# PCB.net
KiCad netlist of a schematic drawn in EAGLE
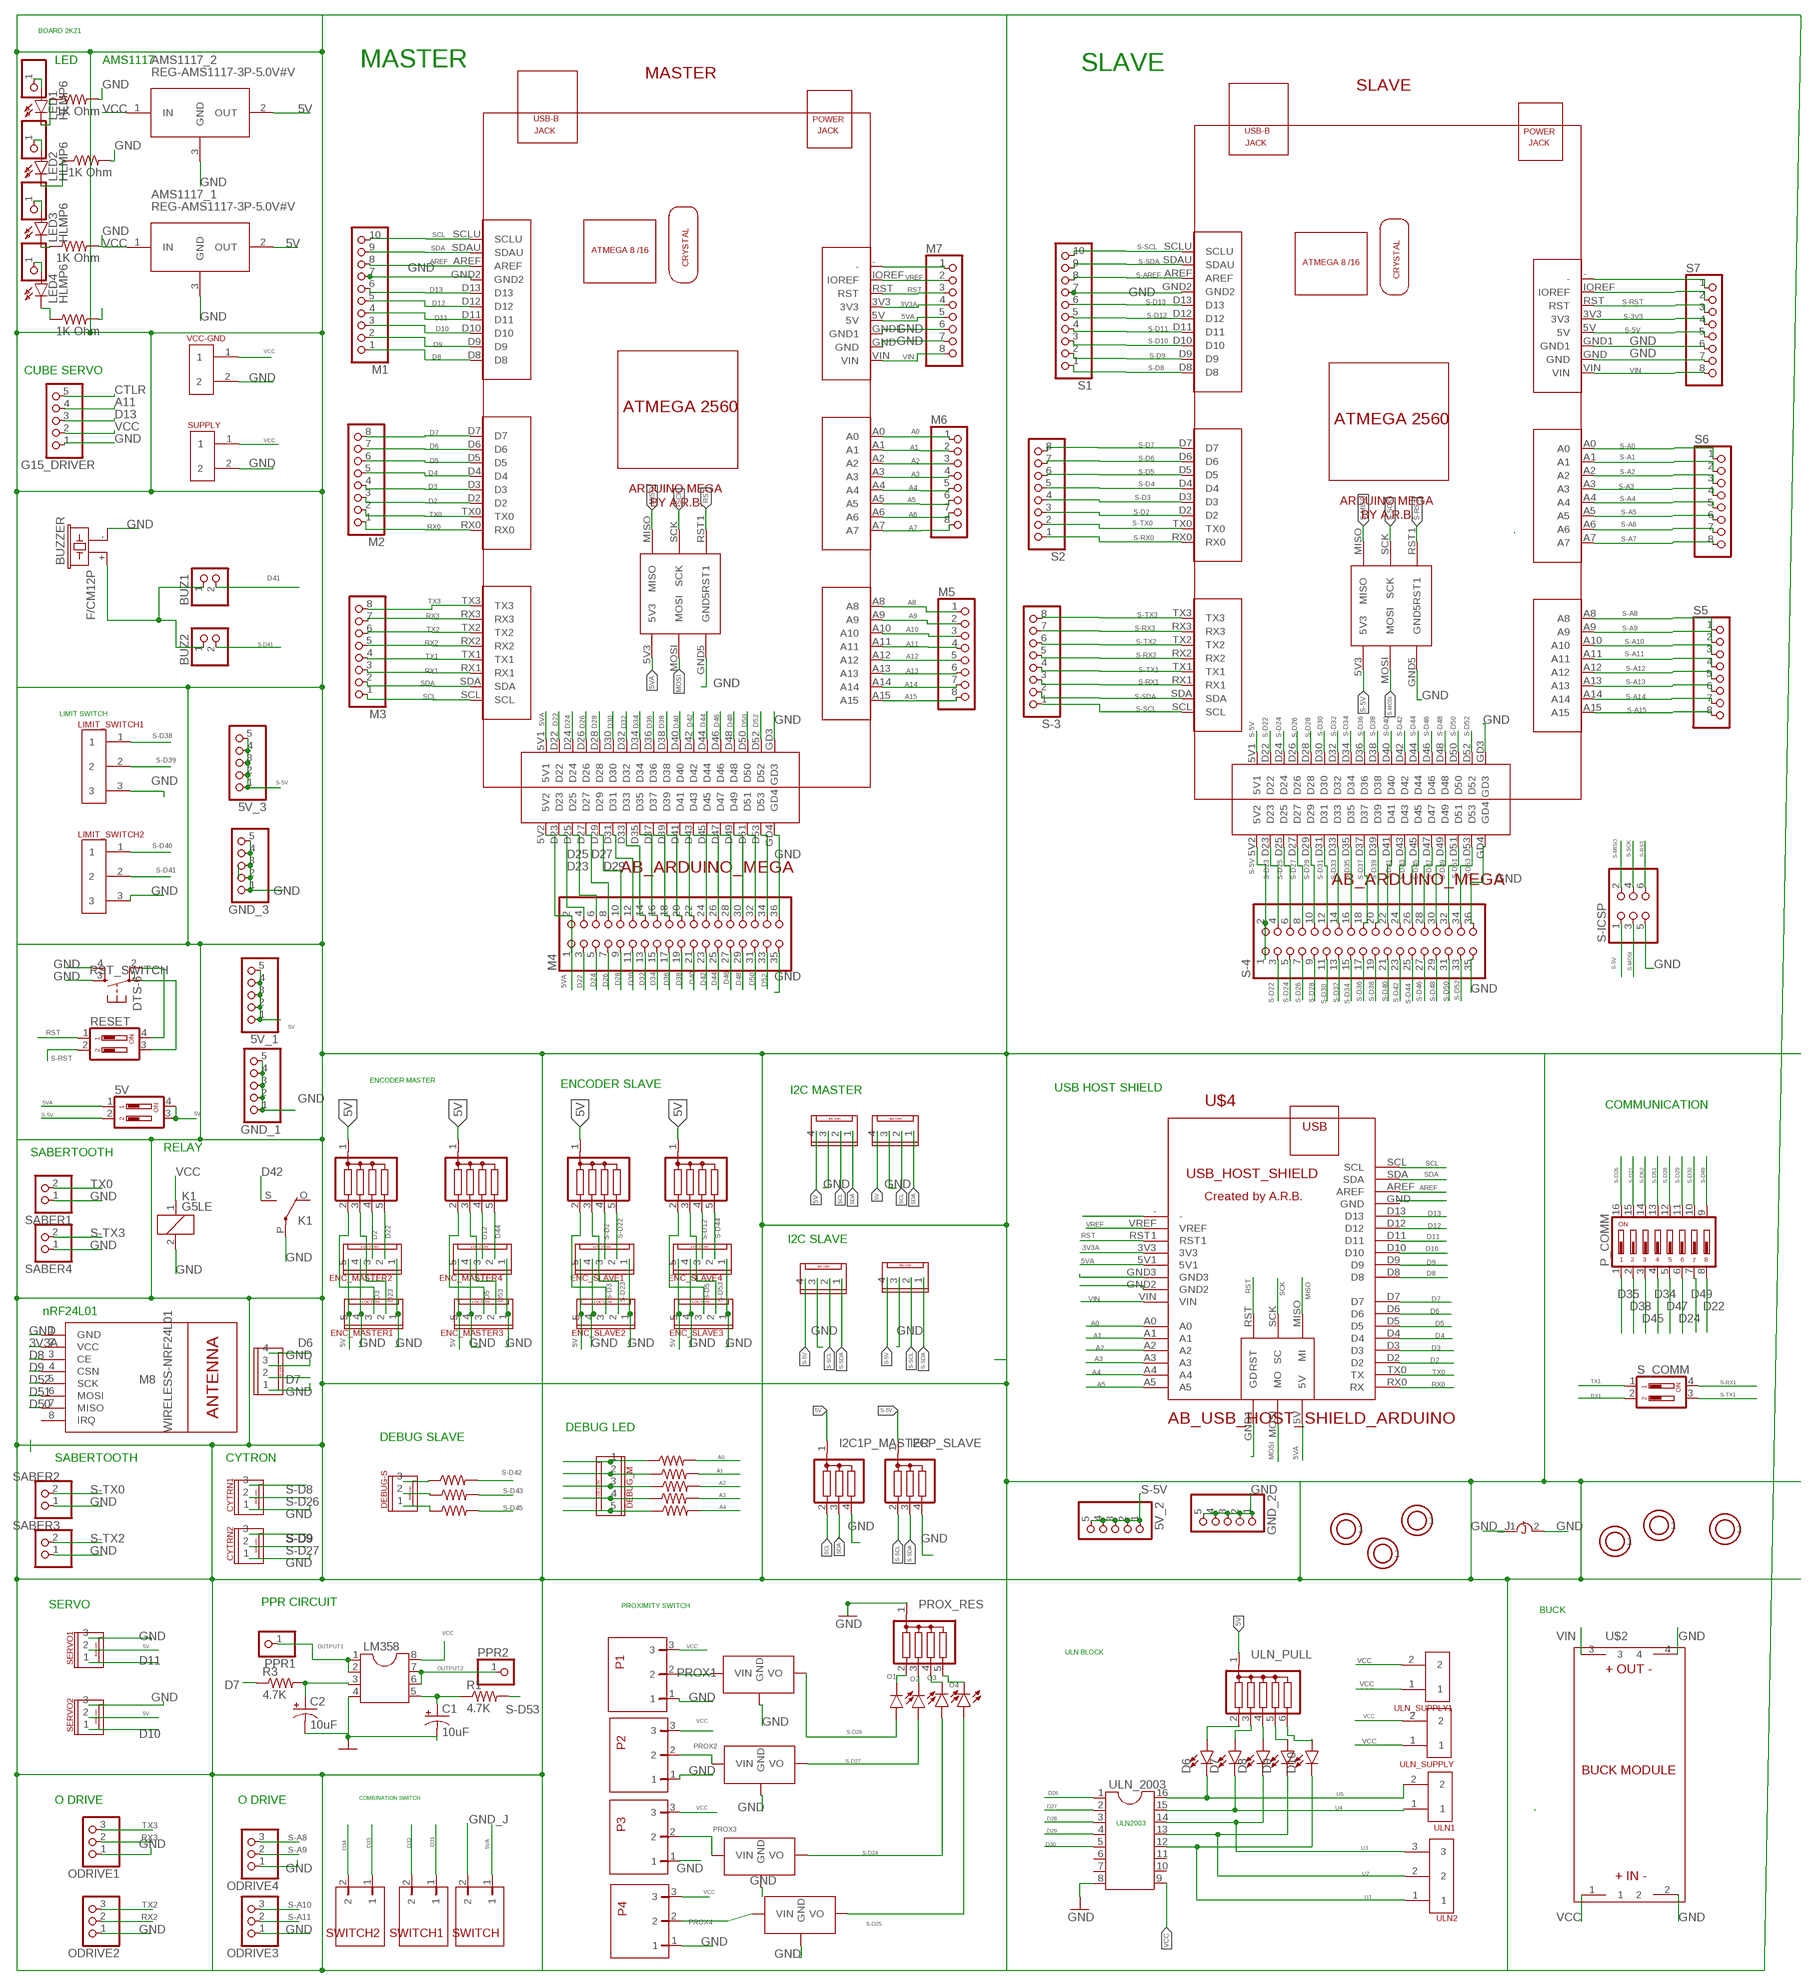
[diagram p0: schematic, sheet 1]

(export (version "E")
  (design (tool "Eeschema 10.0.6"))
  (components
    (comp (ref "5V")
      (value "DIP02YL")
      (footprint "eagle-import:DIP02YL")
      (libsource (lib "eagle-import") (part "DIP02YL"))
    )
    (comp (ref "5V_1")
      (value "PINHD-1X5")
      (footprint "eagle-import:1X05")
      (libsource (lib "eagle-import") (part "PINHD-1X5"))
    )
    (comp (ref "5V_2")
      (value "PINHD-1X5")
      (footprint "eagle-import:1X05")
      (libsource (lib "eagle-import") (part "PINHD-1X5"))
    )
    (comp (ref "5V_3")
      (value "PINHD-1X5")
      (footprint "eagle-import:1X05")
      (libsource (lib "eagle-import") (part "PINHD-1X5"))
    )
    (comp (ref "AMS1117_1")
      (value "REG-AMS1117-3P-5.0V#V")
      (footprint "eagle-import:REG-AMS1117-3P#V")
      (libsource (lib "eagle-import") (part "REG-AMS1117-3P-#V5.0V"))
    )
    (comp (ref "AMS1117_2")
      (value "REG-AMS1117-3P-5.0V#V")
      (footprint "eagle-import:REG-AMS1117-3P#V")
      (libsource (lib "eagle-import") (part "REG-AMS1117-3P-#V5.0V"))
    )
    (comp (ref "BUZ1")
      (value "PINHD-1X2")
      (footprint "eagle-import:1X02")
      (libsource (lib "eagle-import") (part "PINHD-1X2"))
    )
    (comp (ref "BUZ2")
      (value "PINHD-1X2")
      (footprint "eagle-import:1X02")
      (libsource (lib "eagle-import") (part "PINHD-1X2"))
    )
    (comp (ref "BUZZER")
      (value "F/CM12P")
      (footprint "eagle-import:F_CM12P")
      (libsource (lib "eagle-import") (part "F/CM12P"))
    )
    (comp (ref "C1")
      (value "10uF")
      (footprint "eagle-import:CPOL-RADIAL-2.5MM-5MM")
      (libsource (lib "eagle-import") (part "10UF-POLAR-RADIAL-2.5MM-25V-20%"))
    )
    (comp (ref "C2")
      (value "10uF")
      (footprint "eagle-import:CPOL-RADIAL-2.5MM-5MM")
      (libsource (lib "eagle-import") (part "10UF-POLAR-RADIAL-2.5MM-25V-20%"))
    )
    (comp (ref "CYTRN1")
      (value "AB_3PIN_LOC_CONNECTOR")
      (footprint "eagle-import:AB_3PIN_LOC_CONNECTOR")
      (libsource (lib "eagle-import") (part "AB_3PIN_LOC_CONNECTOR"))
    )
    (comp (ref "CYTRN2")
      (value "AB_3PIN_LOC_CONNECTOR")
      (footprint "eagle-import:AB_3PIN_LOC_CONNECTOR")
      (libsource (lib "eagle-import") (part "AB_3PIN_LOC_CONNECTOR"))
    )
    (comp (ref "D1")
      (value "LED-3MM-NO_SILK")
      (footprint "eagle-import:LED_3MM-NS")
      (libsource (lib "eagle-import") (part "LED-3MM-NO_SILK"))
    )
    (comp (ref "D2")
      (value "LED-3MM-NO_SILK")
      (footprint "eagle-import:LED_3MM-NS")
      (libsource (lib "eagle-import") (part "LED-3MM-NO_SILK"))
    )
    (comp (ref "D3")
      (value "LED-3MM-NO_SILK")
      (footprint "eagle-import:LED_3MM-NS")
      (libsource (lib "eagle-import") (part "LED-3MM-NO_SILK"))
    )
    (comp (ref "D6")
      (value "LED-3MM-NO_SILK")
      (footprint "eagle-import:LED_3MM-NS")
      (libsource (lib "eagle-import") (part "LED-3MM-NO_SILK"))
    )
    (comp (ref "D7")
      (value "LED-3MM-NO_SILK")
      (footprint "eagle-import:LED_3MM-NS")
      (libsource (lib "eagle-import") (part "LED-3MM-NO_SILK"))
    )
    (comp (ref "D8")
      (value "LED-3MM-NO_SILK")
      (footprint "eagle-import:LED_3MM-NS")
      (libsource (lib "eagle-import") (part "LED-3MM-NO_SILK"))
    )
    (comp (ref "D9")
      (value "LED-3MM-NO_SILK")
      (footprint "eagle-import:LED_3MM-NS")
      (libsource (lib "eagle-import") (part "LED-3MM-NO_SILK"))
    )
    (comp (ref "D10")
      (value "LED-3MM-NO_SILK")
      (footprint "eagle-import:LED_3MM-NS")
      (libsource (lib "eagle-import") (part "LED-3MM-NO_SILK"))
    )
    (comp (ref "D14")
      (value "LED-3MM-NO_SILK")
      (footprint "eagle-import:LED_3MM-NS")
      (libsource (lib "eagle-import") (part "LED-3MM-NO_SILK"))
    )
    (comp (ref "DEBUG-S")
      (value "AB_3PIN_LOC_CONNECTOR")
      (footprint "eagle-import:AB_3PIN_LOC_CONNECTOR")
      (libsource (lib "eagle-import") (part "AB_3PIN_LOC_CONNECTOR"))
    )
    (comp (ref "DEBUG_M")
      (value "AB_5PIN_LOC_CONNECTOR")
      (footprint "eagle-import:AB_5PIN_LOC_CONNECTOR")
      (libsource (lib "eagle-import") (part "AB_5PIN_LOC_CONNECTOR"))
    )
    (comp (ref "ENC_MASTER1")
      (value "AB_5PIN_LOC_CONNECTOR")
      (footprint "eagle-import:AB_5PIN_LOC_CONNECTOR")
      (libsource (lib "eagle-import") (part "AB_5PIN_LOC_CONNECTOR"))
    )
    (comp (ref "ENC_MASTER2")
      (value "AB_5PIN_LOC_CONNECTOR")
      (footprint "eagle-import:AB_5PIN_LOC_CONNECTOR")
      (libsource (lib "eagle-import") (part "AB_5PIN_LOC_CONNECTOR"))
    )
    (comp (ref "ENC_MASTER3")
      (value "AB_5PIN_LOC_CONNECTOR")
      (footprint "eagle-import:AB_5PIN_LOC_CONNECTOR")
      (libsource (lib "eagle-import") (part "AB_5PIN_LOC_CONNECTOR"))
    )
    (comp (ref "ENC_MASTER4")
      (value "AB_5PIN_LOC_CONNECTOR")
      (footprint "eagle-import:AB_5PIN_LOC_CONNECTOR")
      (libsource (lib "eagle-import") (part "AB_5PIN_LOC_CONNECTOR"))
    )
    (comp (ref "ENC_SLAVE1")
      (value "AB_5PIN_LOC_CONNECTOR")
      (footprint "eagle-import:AB_5PIN_LOC_CONNECTOR")
      (libsource (lib "eagle-import") (part "AB_5PIN_LOC_CONNECTOR"))
    )
    (comp (ref "ENC_SLAVE2")
      (value "AB_5PIN_LOC_CONNECTOR")
      (footprint "eagle-import:AB_5PIN_LOC_CONNECTOR")
      (libsource (lib "eagle-import") (part "AB_5PIN_LOC_CONNECTOR"))
    )
    (comp (ref "ENC_SLAVE3")
      (value "AB_5PIN_LOC_CONNECTOR")
      (footprint "eagle-import:AB_5PIN_LOC_CONNECTOR")
      (libsource (lib "eagle-import") (part "AB_5PIN_LOC_CONNECTOR"))
    )
    (comp (ref "ENC_SLAVE4")
      (value "AB_5PIN_LOC_CONNECTOR")
      (footprint "eagle-import:AB_5PIN_LOC_CONNECTOR")
      (libsource (lib "eagle-import") (part "AB_5PIN_LOC_CONNECTOR"))
    )
    (comp (ref "G15_DRIVER")
      (value "PINHD-1X5")
      (footprint "eagle-import:1X05")
      (libsource (lib "eagle-import") (part "PINHD-1X5"))
    )
    (comp (ref "GND_1")
      (value "PINHD-1X5")
      (footprint "eagle-import:1X05")
      (libsource (lib "eagle-import") (part "PINHD-1X5"))
    )
    (comp (ref "GND_2")
      (value "PINHD-1X5")
      (footprint "eagle-import:1X05")
      (libsource (lib "eagle-import") (part "PINHD-1X5"))
    )
    (comp (ref "GND_3")
      (value "PINHD-1X5")
      (footprint "eagle-import:1X05")
      (libsource (lib "eagle-import") (part "PINHD-1X5"))
    )
    (comp (ref "I2C1P_MASTER")
      (value "G03R")
      (footprint "eagle-import:SIL4")
      (libsource (lib "eagle-import") (part "G03R"))
    )
    (comp (ref "I2CP_SLAVE")
      (value "G03R")
      (footprint "eagle-import:SIL4")
      (libsource (lib "eagle-import") (part "G03R"))
    )
    (comp (ref "IMU_BLOCK2")
      (value "AB_4PIN_LOC_CONNECTOR")
      (footprint "eagle-import:AB_4PIN_LOC_CONNECTOR")
      (libsource (lib "eagle-import") (part "AB_4PIN_LOC_CONNECTOR"))
    )
    (comp (ref "IMU_BLOCK3")
      (value "AB_4PIN_LOC_CONNECTOR")
      (footprint "eagle-import:AB_4PIN_LOC_CONNECTOR")
      (libsource (lib "eagle-import") (part "AB_4PIN_LOC_CONNECTOR"))
    )
    (comp (ref "IMU_BLOCK4")
      (value "AB_4PIN_LOC_CONNECTOR")
      (footprint "eagle-import:AB_4PIN_LOC_CONNECTOR")
      (libsource (lib "eagle-import") (part "AB_4PIN_LOC_CONNECTOR"))
    )
    (comp (ref "IMU_MASTER")
      (value "AB_4PIN_LOC_CONNECTOR")
      (footprint "eagle-import:AB_4PIN_LOC_CONNECTOR")
      (libsource (lib "eagle-import") (part "AB_4PIN_LOC_CONNECTOR"))
    )
    (comp (ref "K1")
      (value "G5LE")
      (footprint "eagle-import:G5LE")
      (libsource (lib "eagle-import") (part "G5LE"))
    )
    (comp (ref "LED1")
      (value "HLMP6")
      (footprint "eagle-import:HLMP6")
      (fields (field (name "MF") "AGILENT TECHNOLOGIES") (field (name "MPN") "HLMP-6500"))
      (libsource (lib "eagle-import") (part "HLMP6"))
    )
    (comp (ref "LED2")
      (value "HLMP6")
      (footprint "eagle-import:HLMP6")
      (fields (field (name "MF") "AGILENT TECHNOLOGIES") (field (name "MPN") "HLMP-6500"))
      (libsource (lib "eagle-import") (part "HLMP6"))
    )
    (comp (ref "LED3")
      (value "HLMP6")
      (footprint "eagle-import:HLMP6")
      (fields (field (name "MF") "AGILENT TECHNOLOGIES") (field (name "MPN") "HLMP-6500"))
      (libsource (lib "eagle-import") (part "HLMP6"))
    )
    (comp (ref "LED4")
      (value "HLMP6")
      (footprint "eagle-import:HLMP6")
      (fields (field (name "MF") "AGILENT TECHNOLOGIES") (field (name "MPN") "HLMP-6500"))
      (libsource (lib "eagle-import") (part "HLMP6"))
    )
    (comp (ref "LIMIT_SWITCH1")
      (value "AB_SCREW_TER_5MM_3PIN")
      (footprint "eagle-import:AB_SCREW_TER_5MM_3PIN")
      (libsource (lib "eagle-import") (part "AB_SCREW_TER_5MM_3PIN"))
    )
    (comp (ref "LIMIT_SWITCH2")
      (value "AB_SCREW_TER_5MM_3PIN")
      (footprint "eagle-import:AB_SCREW_TER_5MM_3PIN")
      (libsource (lib "eagle-import") (part "AB_SCREW_TER_5MM_3PIN"))
    )
    (comp (ref "LM358")
      (value "DIL8")
      (footprint "eagle-import:DIL08")
      (libsource (lib "eagle-import") (part "DIL8"))
    )
    (comp (ref "M1")
      (value "PINHD-1X10")
      (footprint "eagle-import:1X10")
      (libsource (lib "eagle-import") (part "PINHD-1X10"))
    )
    (comp (ref "M2")
      (value "PINHD-1X8")
      (footprint "eagle-import:1X08")
      (libsource (lib "eagle-import") (part "PINHD-1X8"))
    )
    (comp (ref "M3")
      (value "PINHD-1X8")
      (footprint "eagle-import:1X08")
      (libsource (lib "eagle-import") (part "PINHD-1X8"))
    )
    (comp (ref "M4")
      (value "PINHD-2X18")
      (footprint "eagle-import:2X18")
      (libsource (lib "eagle-import") (part "PINHD-2X18"))
    )
    (comp (ref "M5")
      (value "PINHD-1X8")
      (footprint "eagle-import:1X08")
      (libsource (lib "eagle-import") (part "PINHD-1X8"))
    )
    (comp (ref "M6")
      (value "PINHD-1X8")
      (footprint "eagle-import:1X08")
      (libsource (lib "eagle-import") (part "PINHD-1X8"))
    )
    (comp (ref "M7")
      (value "PINHD-1X8")
      (footprint "eagle-import:1X08")
      (libsource (lib "eagle-import") (part "PINHD-1X8"))
    )
    (comp (ref "M8")
      (value "WIRELESS-NRF24L01")
      (footprint "eagle-import:WIRELESS-NRF24L01")
      (libsource (lib "eagle-import") (part "WIRELESS-NRF24L01"))
    )
    (comp (ref "MASTER")
      (value "AB_ARDUINO_MEGA")
      (footprint "eagle-import:AB_ARDUINO_MEGA")
      (libsource (lib "eagle-import") (part "AB_ARDUINO_MEGA"))
    )
    (comp (ref "ODRIVE1")
      (value "PINHD-1X3")
      (footprint "eagle-import:1X03")
      (libsource (lib "eagle-import") (part "PINHD-1X3"))
    )
    (comp (ref "ODRIVE2")
      (value "PINHD-1X3")
      (footprint "eagle-import:1X03")
      (libsource (lib "eagle-import") (part "PINHD-1X3"))
    )
    (comp (ref "ODRIVE3")
      (value "PINHD-1X3")
      (footprint "eagle-import:1X03")
      (libsource (lib "eagle-import") (part "PINHD-1X3"))
    )
    (comp (ref "ODRIVE4")
      (value "PINHD-1X3")
      (footprint "eagle-import:1X03")
      (libsource (lib "eagle-import") (part "PINHD-1X3"))
    )
    (comp (ref "P1")
      (value "P1")
      (footprint "eagle-import:AB_RIGHT_TER_BLK_3PIN")
      (libsource (lib "eagle-import") (part "AB_RIGHT_TER_BLK_3PIN"))
    )
    (comp (ref "P2")
      (value "P2")
      (footprint "eagle-import:AB_RIGHT_TER_BLK_3PIN")
      (libsource (lib "eagle-import") (part "AB_RIGHT_TER_BLK_3PIN"))
    )
    (comp (ref "P3")
      (value "P3")
      (footprint "eagle-import:AB_RIGHT_TER_BLK_3PIN")
      (libsource (lib "eagle-import") (part "AB_RIGHT_TER_BLK_3PIN"))
    )
    (comp (ref "P4")
      (value "P4")
      (footprint "eagle-import:AB_RIGHT_TER_BLK_3PIN")
      (libsource (lib "eagle-import") (part "AB_RIGHT_TER_BLK_3PIN"))
    )
    (comp (ref "PPR1")
      (value "PINHD-1X1")
      (footprint "eagle-import:1X01")
      (libsource (lib "eagle-import") (part "PINHD-1X1"))
    )
    (comp (ref "PPR2")
      (value "PINHD-1X1")
      (footprint "eagle-import:1X01")
      (libsource (lib "eagle-import") (part "PINHD-1X1"))
    )
    (comp (ref "PPR5")
      (value "PINHD-1X1")
      (footprint "eagle-import:1X01")
      (libsource (lib "eagle-import") (part "PINHD-1X1"))
    )
    (comp (ref "PPR6")
      (value "PINHD-1X1")
      (footprint "eagle-import:1X01")
      (libsource (lib "eagle-import") (part "PINHD-1X1"))
    )
    (comp (ref "PPR7")
      (value "PINHD-1X1")
      (footprint "eagle-import:1X01")
      (libsource (lib "eagle-import") (part "PINHD-1X1"))
    )
    (comp (ref "PPR8")
      (value "PINHD-1X1")
      (footprint "eagle-import:1X01")
      (libsource (lib "eagle-import") (part "PINHD-1X1"))
    )
    (comp (ref "PROX_RES")
      (value "G04R")
      (footprint "eagle-import:SIL5")
      (libsource (lib "eagle-import") (part "G04R"))
    )
    (comp (ref "PULL_MASTER1")
      (value "G04R")
      (footprint "eagle-import:SIL5")
      (libsource (lib "eagle-import") (part "G04R"))
    )
    (comp (ref "PULL_MASTER2")
      (value "G04R")
      (footprint "eagle-import:SIL5")
      (libsource (lib "eagle-import") (part "G04R"))
    )
    (comp (ref "PULL_SLAVE3")
      (value "G04R")
      (footprint "eagle-import:SIL5")
      (libsource (lib "eagle-import") (part "G04R"))
    )
    (comp (ref "P_COMM")
      (value "DIP08YL")
      (footprint "eagle-import:DIP08YL")
      (libsource (lib "eagle-import") (part "DIP08YL"))
    )
    (comp (ref "R1")
      (value "4.7K")
      (footprint "eagle-import:0204_7")
      (libsource (lib "eagle-import") (part "R-US_0204/7"))
    )
    (comp (ref "R2")
      (value "R-US_0204/7")
      (footprint "eagle-import:0204_7")
      (libsource (lib "eagle-import") (part "R-US_0204/7"))
    )
    (comp (ref "R3")
      (value "4.7K")
      (footprint "eagle-import:0204_7")
      (libsource (lib "eagle-import") (part "R-US_0204/7"))
    )
    (comp (ref "R4")
      (value "R-US_0204/7")
      (footprint "eagle-import:0204_7")
      (libsource (lib "eagle-import") (part "R-US_0204/7"))
    )
    (comp (ref "R5")
      (value "R-US_0204/7")
      (footprint "eagle-import:0204_7")
      (libsource (lib "eagle-import") (part "R-US_0204/7"))
    )
    (comp (ref "R6")
      (value "R-US_0204/7")
      (footprint "eagle-import:0204_7")
      (libsource (lib "eagle-import") (part "R-US_0204/7"))
    )
    (comp (ref "R7")
      (value "R-US_0204/7")
      (footprint "eagle-import:0204_7")
      (libsource (lib "eagle-import") (part "R-US_0204/7"))
    )
    (comp (ref "R8")
      (value "R-US_0204/7")
      (footprint "eagle-import:0204_7")
      (libsource (lib "eagle-import") (part "R-US_0204/7"))
    )
    (comp (ref "R9")
      (value "R-US_0204/7")
      (footprint "eagle-import:0204_7")
      (libsource (lib "eagle-import") (part "R-US_0204/7"))
    )
    (comp (ref "R10")
      (value "R-US_0204/7")
      (footprint "eagle-import:0204_7")
      (libsource (lib "eagle-import") (part "R-US_0204/7"))
    )
    (comp (ref "R13")
      (value "1K Ohm")
      (footprint "eagle-import:0204_7")
      (libsource (lib "eagle-import") (part "R-US_0204/7"))
    )
    (comp (ref "R14")
      (value "1K Ohm")
      (footprint "eagle-import:0204_7")
      (libsource (lib "eagle-import") (part "R-US_0204/7"))
    )
    (comp (ref "R15")
      (value "1K Ohm")
      (footprint "eagle-import:0204_7")
      (libsource (lib "eagle-import") (part "R-US_0204/7"))
    )
    (comp (ref "R16")
      (value "1K Ohm")
      (footprint "eagle-import:0204_7")
      (libsource (lib "eagle-import") (part "R-US_0204/7"))
    )
    (comp (ref "RESET")
      (value "DIP02YL")
      (footprint "eagle-import:DIP02YL")
      (libsource (lib "eagle-import") (part "DIP02YL"))
    )
    (comp (ref "RST_SWITCH")
      (value "DTS-6")
      (footprint "eagle-import:DTS-6")
      (libsource (lib "eagle-import") (part "DTS-6"))
    )
    (comp (ref "S-3")
      (value "PINHD-1X8")
      (footprint "eagle-import:1X08")
      (libsource (lib "eagle-import") (part "PINHD-1X8"))
    )
    (comp (ref "S-4")
      (value "PINHD-2X18")
      (footprint "eagle-import:2X18")
      (libsource (lib "eagle-import") (part "PINHD-2X18"))
    )
    (comp (ref "S-ICSP")
      (value "PINHD-2X3")
      (footprint "eagle-import:2X03")
      (libsource (lib "eagle-import") (part "PINHD-2X3"))
    )
    (comp (ref "S1")
      (value "PINHD-1X10")
      (footprint "eagle-import:1X10")
      (libsource (lib "eagle-import") (part "PINHD-1X10"))
    )
    (comp (ref "S2")
      (value "PINHD-1X8")
      (footprint "eagle-import:1X08")
      (libsource (lib "eagle-import") (part "PINHD-1X8"))
    )
    (comp (ref "S5")
      (value "PINHD-1X8")
      (footprint "eagle-import:1X08")
      (libsource (lib "eagle-import") (part "PINHD-1X8"))
    )
    (comp (ref "S6")
      (value "PINHD-1X8")
      (footprint "eagle-import:1X08")
      (libsource (lib "eagle-import") (part "PINHD-1X8"))
    )
    (comp (ref "S7")
      (value "PINHD-1X8")
      (footprint "eagle-import:1X08")
      (libsource (lib "eagle-import") (part "PINHD-1X8"))
    )
    (comp (ref "SABER1")
      (value "PINHD-1X2")
      (footprint "eagle-import:1X02")
      (libsource (lib "eagle-import") (part "PINHD-1X2"))
    )
    (comp (ref "SABER2")
      (value "PINHD-1X2")
      (footprint "eagle-import:1X02")
      (libsource (lib "eagle-import") (part "PINHD-1X2"))
    )
    (comp (ref "SABER3")
      (value "PINHD-1X2")
      (footprint "eagle-import:1X02")
      (libsource (lib "eagle-import") (part "PINHD-1X2"))
    )
    (comp (ref "SABER4")
      (value "PINHD-1X2")
      (footprint "eagle-import:1X02")
      (libsource (lib "eagle-import") (part "PINHD-1X2"))
    )
    (comp (ref "SERVO1")
      (value "AB_3PIN_LOC_CONNECTOR")
      (footprint "eagle-import:AB_3PIN_LOC_CONNECTOR")
      (libsource (lib "eagle-import") (part "AB_3PIN_LOC_CONNECTOR"))
    )
    (comp (ref "SERVO2")
      (value "AB_3PIN_LOC_CONNECTOR")
      (footprint "eagle-import:AB_3PIN_LOC_CONNECTOR")
      (libsource (lib "eagle-import") (part "AB_3PIN_LOC_CONNECTOR"))
    )
    (comp (ref "SLAVE")
      (value "AB_ARDUINO_MEGA")
      (footprint "eagle-import:AB_ARDUINO_MEGA")
      (libsource (lib "eagle-import") (part "AB_ARDUINO_MEGA"))
    )
    (comp (ref "STEPPER")
      (value "AB_4PIN_LOC_CONNECTOR")
      (footprint "eagle-import:AB_4PIN_LOC_CONNECTOR")
      (libsource (lib "eagle-import") (part "AB_4PIN_LOC_CONNECTOR"))
    )
    (comp (ref "SUPPLY")
      (value "AB_SCREW_TERMINAL_5MM_2PIN")
      (footprint "eagle-import:AB_SCREW_TERMINAL_5MM_2PIN")
      (libsource (lib "eagle-import") (part "AB_SCREW_TERMINAL_5MM_2PIN"))
    )
    (comp (ref "SWITCH")
      (value "AB_RIGHT_TER_BLK")
      (footprint "eagle-import:AB_RIGHT_TER_BLK")
      (libsource (lib "eagle-import") (part "AB_RIGHT_TER_BLK"))
    )
    (comp (ref "SWITCH1")
      (value "AB_RIGHT_TER_BLK")
      (footprint "eagle-import:AB_RIGHT_TER_BLK")
      (libsource (lib "eagle-import") (part "AB_RIGHT_TER_BLK"))
    )
    (comp (ref "SWITCH2")
      (value "AB_RIGHT_TER_BLK")
      (footprint "eagle-import:AB_RIGHT_TER_BLK")
      (libsource (lib "eagle-import") (part "AB_RIGHT_TER_BLK"))
    )
    (comp (ref "S_COMM")
      (value "DIP02YL")
      (footprint "eagle-import:DIP02YL")
      (libsource (lib "eagle-import") (part "DIP02YL"))
    )
    (comp (ref "S_ENC_PULL1")
      (value "G04R")
      (footprint "eagle-import:SIL5")
      (libsource (lib "eagle-import") (part "G04R"))
    )
    (comp (ref "U$2")
      (value "BUCK_MODULEWITH_SMDPADS&THROUGHHOLES")
      (footprint "eagle-import:BUCK_MODULE")
      (libsource (lib "eagle-import") (part "BUCK_MODULEWITH_SMDPADS&THROUGHHOLES"))
    )
    (comp (ref "U$3")
      (value "PLATED_DRILL_3.5MM")
      (footprint "eagle-import:PLATED_DRILL_3.5MM")
      (libsource (lib "eagle-import") (part "PLATED_DRILL_3.5MM"))
    )
    (comp (ref "U$4")
      (value "AB_USB_HOST_SHIELD_ARDUINO")
      (footprint "eagle-import:AB_USB_HOST_SHIELD_ARDUINO")
      (libsource (lib "eagle-import") (part "AB_USB_HOST_SHIELD_ARDUINO"))
    )
    (comp (ref "U$5")
      (value "PLATED_DRILL_3.5MM")
      (footprint "eagle-import:PLATED_DRILL_3.5MM")
      (libsource (lib "eagle-import") (part "PLATED_DRILL_3.5MM"))
    )
    (comp (ref "U$6")
      (value "PLATED_DRILL_3.5MM")
      (footprint "eagle-import:PLATED_DRILL_3.5MM")
      (libsource (lib "eagle-import") (part "PLATED_DRILL_3.5MM"))
    )
    (comp (ref "U$7")
      (value "PLATED_DRILL_3.5MM")
      (footprint "eagle-import:PLATED_DRILL_3.5MM")
      (libsource (lib "eagle-import") (part "PLATED_DRILL_3.5MM"))
    )
    (comp (ref "U$8")
      (value "PLATED_DRILL_3.5MM")
      (footprint "eagle-import:PLATED_DRILL_3.5MM")
      (libsource (lib "eagle-import") (part "PLATED_DRILL_3.5MM"))
    )
    (comp (ref "U$9")
      (value "PLATED_DRILL_3.5MM")
      (footprint "eagle-import:PLATED_DRILL_3.5MM")
      (libsource (lib "eagle-import") (part "PLATED_DRILL_3.5MM"))
    )
    (comp (ref "U$23")
      (value "AB_7805_FLAT")
      (footprint "eagle-import:AB_7805_FLAT")
      (libsource (lib "eagle-import") (part "AB_7805_FLAT"))
    )
    (comp (ref "U$24")
      (value "AB_7805_FLAT")
      (footprint "eagle-import:AB_7805_FLAT")
      (libsource (lib "eagle-import") (part "AB_7805_FLAT"))
    )
    (comp (ref "U$25")
      (value "AB_7805_FLAT")
      (footprint "eagle-import:AB_7805_FLAT")
      (libsource (lib "eagle-import") (part "AB_7805_FLAT"))
    )
    (comp (ref "U$26")
      (value "AB_7805_FLAT")
      (footprint "eagle-import:AB_7805_FLAT")
      (libsource (lib "eagle-import") (part "AB_7805_FLAT"))
    )
    (comp (ref "U$35")
      (value "AB_JUMPER_ONE_WAY")
      (footprint "eagle-import:AB_JUMPER_ONE_WAY")
      (libsource (lib "eagle-import") (part "AB_JUMPER_ONE_WAY"))
    )
    (comp (ref "ULN1")
      (value "AB_SCREW_TERMINAL_5MM_2PIN")
      (footprint "eagle-import:AB_SCREW_TERMINAL_5MM_2PIN")
      (libsource (lib "eagle-import") (part "AB_SCREW_TERMINAL_5MM_2PIN"))
    )
    (comp (ref "ULN2")
      (value "AB_SCREW_TER_5MM_3PIN")
      (footprint "eagle-import:AB_SCREW_TER_5MM_3PIN")
      (libsource (lib "eagle-import") (part "AB_SCREW_TER_5MM_3PIN"))
    )
    (comp (ref "ULN_2003")
      (value "DIL16")
      (footprint "eagle-import:DIL16")
      (libsource (lib "eagle-import") (part "DIL16"))
    )
    (comp (ref "ULN_PULL")
      (value "G05R")
      (footprint "eagle-import:SIL6")
      (libsource (lib "eagle-import") (part "G05R"))
    )
    (comp (ref "ULN_SUPPLY")
      (value "AB_SCREW_TERMINAL_5MM_2PIN")
      (footprint "eagle-import:AB_SCREW_TERMINAL_5MM_2PIN")
      (libsource (lib "eagle-import") (part "AB_SCREW_TERMINAL_5MM_2PIN"))
    )
    (comp (ref "ULN_SUPPLY1")
      (value "AB_SCREW_TERMINAL_5MM_2PIN")
      (footprint "eagle-import:AB_SCREW_TERMINAL_5MM_2PIN")
      (libsource (lib "eagle-import") (part "AB_SCREW_TERMINAL_5MM_2PIN"))
    )
    (comp (ref "VCC-GND")
      (value "AB_SCREW_TERMINAL_5MM_2PIN")
      (footprint "eagle-import:AB_SCREW_TERMINAL_5MM_2PIN")
      (libsource (lib "eagle-import") (part "AB_SCREW_TERMINAL_5MM_2PIN"))
    )
  )
  (nets
    (net (code "1") (name "/3V3A") (class "Default")
      (node (ref "M7") (pin "4") (pinfunction "4_4") (pintype "passive"))
      (node (ref "M8") (pin "2") (pinfunction "VCC_2") (pintype "power_in"))
      (node (ref "MASTER") (pin "3V3") (pinfunction "3V3_3V3") (pintype "bidirectional"))
      (node (ref "U$4") (pin "3V3") (pinfunction "3V3_3V3") (pintype "bidirectional"))
    )
    (net (code "2") (name "/A0") (class "Default")
      (node (ref "M6") (pin "1") (pinfunction "1_1") (pintype "passive"))
      (node (ref "MASTER") (pin "A0") (pinfunction "A0_A0") (pintype "bidirectional"))
      (node (ref "R2") (pin "2") (pinfunction "2_2") (pintype "passive"))
      (node (ref "U$4") (pin "A0") (pinfunction "A0_A0") (pintype "bidirectional"))
    )
    (net (code "3") (name "/A1") (class "Default")
      (node (ref "M6") (pin "2") (pinfunction "2_2") (pintype "passive"))
      (node (ref "MASTER") (pin "A1") (pinfunction "A1_A1") (pintype "bidirectional"))
      (node (ref "R4") (pin "2") (pinfunction "2_2") (pintype "passive"))
      (node (ref "U$4") (pin "A1") (pinfunction "A1_A1") (pintype "bidirectional"))
    )
    (net (code "4") (name "/A2") (class "Default")
      (node (ref "M6") (pin "3") (pinfunction "3_3") (pintype "passive"))
      (node (ref "MASTER") (pin "A2") (pinfunction "A2_A2") (pintype "bidirectional"))
      (node (ref "R5") (pin "2") (pinfunction "2_2") (pintype "passive"))
      (node (ref "U$4") (pin "A2") (pinfunction "A2_A2") (pintype "bidirectional"))
    )
    (net (code "5") (name "/A3") (class "Default")
      (node (ref "M6") (pin "4") (pinfunction "4_4") (pintype "passive"))
      (node (ref "MASTER") (pin "A3") (pinfunction "A3_A3") (pintype "bidirectional"))
      (node (ref "R6") (pin "2") (pinfunction "2_2") (pintype "passive"))
      (node (ref "U$4") (pin "A3") (pinfunction "A3_A3") (pintype "bidirectional"))
    )
    (net (code "6") (name "/A4") (class "Default")
      (node (ref "M6") (pin "5") (pinfunction "5_5") (pintype "passive"))
      (node (ref "MASTER") (pin "A4") (pinfunction "A4_A4") (pintype "bidirectional"))
      (node (ref "R7") (pin "2") (pinfunction "2_2") (pintype "passive"))
      (node (ref "U$4") (pin "A4") (pinfunction "A4_A4") (pintype "bidirectional"))
    )
    (net (code "7") (name "/A5") (class "Default")
      (node (ref "M6") (pin "6") (pinfunction "6_6") (pintype "passive"))
      (node (ref "MASTER") (pin "A5") (pinfunction "A5_A5") (pintype "bidirectional"))
      (node (ref "U$4") (pin "A5") (pinfunction "A5_A5") (pintype "bidirectional"))
    )
    (net (code "8") (name "/A6") (class "Default")
      (node (ref "M6") (pin "7") (pinfunction "7_7") (pintype "passive"))
      (node (ref "MASTER") (pin "A6") (pinfunction "A6_A6") (pintype "bidirectional"))
    )
    (net (code "9") (name "/A7") (class "Default")
      (node (ref "M6") (pin "8") (pinfunction "8_8") (pintype "passive"))
      (node (ref "MASTER") (pin "A7") (pinfunction "A7_A7") (pintype "bidirectional"))
    )
    (net (code "10") (name "/A8") (class "Default")
      (node (ref "M5") (pin "1") (pinfunction "1_1") (pintype "passive"))
      (node (ref "MASTER") (pin "A8") (pinfunction "A8_A8") (pintype "bidirectional"))
    )
    (net (code "11") (name "/A9") (class "Default")
      (node (ref "M5") (pin "2") (pinfunction "2_2") (pintype "passive"))
      (node (ref "MASTER") (pin "A9") (pinfunction "A9_A9") (pintype "bidirectional"))
    )
    (net (code "12") (name "/A10") (class "Default")
      (node (ref "M5") (pin "3") (pinfunction "3_3") (pintype "passive"))
      (node (ref "MASTER") (pin "A10") (pinfunction "A10_A10") (pintype "bidirectional"))
    )
    (net (code "13") (name "/A11") (class "Default")
      (node (ref "G15_DRIVER") (pin "4") (pinfunction "4_4") (pintype "passive"))
      (node (ref "M5") (pin "4") (pinfunction "4_4") (pintype "passive"))
      (node (ref "MASTER") (pin "A11") (pinfunction "A11_A11") (pintype "bidirectional"))
    )
    (net (code "14") (name "/A12") (class "Default")
      (node (ref "M5") (pin "5") (pinfunction "5_5") (pintype "passive"))
      (node (ref "MASTER") (pin "A12") (pinfunction "A12_A12") (pintype "bidirectional"))
    )
    (net (code "15") (name "/A13") (class "Default")
      (node (ref "M5") (pin "6") (pinfunction "6_6") (pintype "passive"))
      (node (ref "MASTER") (pin "A13") (pinfunction "A13_A13") (pintype "bidirectional"))
    )
    (net (code "16") (name "/A14") (class "Default")
      (node (ref "M5") (pin "7") (pinfunction "7_7") (pintype "passive"))
      (node (ref "MASTER") (pin "A14") (pinfunction "A14_A14") (pintype "bidirectional"))
    )
    (net (code "17") (name "/A15") (class "Default")
      (node (ref "M5") (pin "8") (pinfunction "8_8") (pintype "passive"))
      (node (ref "MASTER") (pin "A15") (pinfunction "A15_A15") (pintype "bidirectional"))
    )
    (net (code "18") (name "/AREF") (class "Default")
      (node (ref "M1") (pin "8") (pinfunction "8_8") (pintype "passive"))
      (node (ref "MASTER") (pin "AREF") (pinfunction "AREF_AREF") (pintype "bidirectional"))
      (node (ref "U$4") (pin "AREF") (pinfunction "AREF_AREF") (pintype "bidirectional"))
    )
    (net (code "19") (name "/CTLR") (class "Default")
      (node (ref "G15_DRIVER") (pin "5") (pinfunction "5_5") (pintype "passive"))
    )
    (net (code "20") (name "/D2") (class "Default")
      (node (ref "ENC_MASTER2") (pin "3") (pinfunction "3_3") (pintype "bidirectional"))
      (node (ref "M2") (pin "3") (pinfunction "3_3") (pintype "passive"))
      (node (ref "MASTER") (pin "D2") (pinfunction "D2_D2") (pintype "bidirectional"))
      (node (ref "PULL_MASTER1") (pin "4") (pinfunction "4_4") (pintype "passive"))
      (node (ref "U$4") (pin "D2") (pinfunction "D2_D2") (pintype "bidirectional"))
    )
    (net (code "21") (name "/D3") (class "Default")
      (node (ref "ENC_MASTER1") (pin "3") (pinfunction "3_3") (pintype "bidirectional"))
      (node (ref "M2") (pin "4") (pinfunction "4_4") (pintype "passive"))
      (node (ref "MASTER") (pin "D3") (pinfunction "D3_D3") (pintype "bidirectional"))
      (node (ref "PULL_MASTER1") (pin "2") (pinfunction "2_2") (pintype "passive"))
      (node (ref "U$4") (pin "D3") (pinfunction "D3_D3") (pintype "bidirectional"))
    )
    (net (code "22") (name "/D4") (class "Default")
      (node (ref "M2") (pin "5") (pinfunction "5_5") (pintype "passive"))
      (node (ref "MASTER") (pin "D4") (pinfunction "D4_D4") (pintype "bidirectional"))
      (node (ref "U$4") (pin "D4") (pinfunction "D4_D4") (pintype "bidirectional"))
    )
    (net (code "23") (name "/D5") (class "Default")
      (node (ref "ENC_MASTER3") (pin "3") (pinfunction "3_3") (pintype "bidirectional"))
      (node (ref "M2") (pin "6") (pinfunction "6_6") (pintype "passive"))
      (node (ref "MASTER") (pin "D5") (pinfunction "D5_D5") (pintype "bidirectional"))
      (node (ref "PULL_MASTER2") (pin "2") (pinfunction "2_2") (pintype "passive"))
      (node (ref "U$4") (pin "D5") (pinfunction "D5_D5") (pintype "bidirectional"))
    )
    (net (code "24") (name "/D6") (class "Default")
      (node (ref "M2") (pin "7") (pinfunction "7_7") (pintype "passive"))
      (node (ref "MASTER") (pin "D6") (pinfunction "D6_D6") (pintype "bidirectional"))
      (node (ref "STEPPER") (pin "4") (pinfunction "4_4") (pintype "bidirectional"))
      (node (ref "U$4") (pin "D6") (pinfunction "D6_D6") (pintype "bidirectional"))
    )
    (net (code "25") (name "/D7") (class "Default")
      (node (ref "M2") (pin "8") (pinfunction "8_8") (pintype "passive"))
      (node (ref "MASTER") (pin "D7") (pinfunction "D7_D7") (pintype "bidirectional"))
      (node (ref "R3") (pin "1") (pinfunction "1_1") (pintype "passive"))
      (node (ref "STEPPER") (pin "2") (pinfunction "2_2") (pintype "bidirectional"))
      (node (ref "U$4") (pin "D7") (pinfunction "D7_D7") (pintype "bidirectional"))
    )
    (net (code "26") (name "/D8") (class "Default")
      (node (ref "M1") (pin "1") (pinfunction "1_1") (pintype "passive"))
      (node (ref "M8") (pin "3") (pinfunction "CE_3") (pintype "bidirectional"))
      (node (ref "MASTER") (pin "D8") (pinfunction "D8_D8") (pintype "bidirectional"))
      (node (ref "U$4") (pin "D8") (pinfunction "D8_D8") (pintype "bidirectional"))
    )
    (net (code "27") (name "/D9") (class "Default")
      (node (ref "M1") (pin "2") (pinfunction "2_2") (pintype "passive"))
      (node (ref "M8") (pin "4") (pinfunction "CSN_4") (pintype "bidirectional"))
      (node (ref "MASTER") (pin "D9") (pinfunction "D9_D9") (pintype "bidirectional"))
      (node (ref "U$4") (pin "D9") (pinfunction "D9_D9") (pintype "bidirectional"))
    )
    (net (code "28") (name "/D10") (class "Default")
      (node (ref "M1") (pin "3") (pinfunction "3_3") (pintype "passive"))
      (node (ref "MASTER") (pin "D10") (pinfunction "D10_D10") (pintype "bidirectional"))
      (node (ref "SERVO2") (pin "1") (pinfunction "1_1") (pintype "bidirectional"))
      (node (ref "U$4") (pin "D10") (pinfunction "D10_D10") (pintype "bidirectional"))
    )
    (net (code "29") (name "/D11") (class "Default")
      (node (ref "M1") (pin "4") (pinfunction "4_4") (pintype "passive"))
      (node (ref "MASTER") (pin "D11") (pinfunction "D11_D11") (pintype "bidirectional"))
      (node (ref "SERVO1") (pin "1") (pinfunction "1_1") (pintype "bidirectional"))
      (node (ref "U$4") (pin "D11") (pinfunction "D11_D11") (pintype "bidirectional"))
    )
    (net (code "30") (name "/D12") (class "Default")
      (node (ref "ENC_MASTER4") (pin "3") (pinfunction "3_3") (pintype "bidirectional"))
      (node (ref "M1") (pin "5") (pinfunction "5_5") (pintype "passive"))
      (node (ref "MASTER") (pin "D12") (pinfunction "D12_D12") (pintype "bidirectional"))
      (node (ref "PULL_MASTER2") (pin "4") (pinfunction "4_4") (pintype "passive"))
      (node (ref "U$4") (pin "D12") (pinfunction "D12_D12") (pintype "bidirectional"))
    )
    (net (code "31") (name "/D13") (class "Default")
      (node (ref "G15_DRIVER") (pin "3") (pinfunction "3_3") (pintype "passive"))
      (node (ref "M1") (pin "6") (pinfunction "6_6") (pintype "passive"))
      (node (ref "MASTER") (pin "D13") (pinfunction "D13_D13") (pintype "bidirectional"))
      (node (ref "U$4") (pin "D13") (pinfunction "D13_D13") (pintype "bidirectional"))
    )
    (net (code "32") (name "/D22") (class "Default")
      (node (ref "ENC_MASTER2") (pin "2") (pinfunction "2_2") (pintype "bidirectional"))
      (node (ref "M4") (pin "3") (pinfunction "3_3") (pintype "passive"))
      (node (ref "MASTER") (pin "D22") (pinfunction "D22_D22") (pintype "bidirectional"))
      (node (ref "PULL_MASTER1") (pin "5") (pinfunction "5_5") (pintype "passive"))
      (node (ref "P_COMM") (pin "8") (pinfunction "8_8") (pintype "passive"))
    )
    (net (code "33") (name "/D23") (class "Default")
      (node (ref "ENC_MASTER1") (pin "2") (pinfunction "2_2") (pintype "bidirectional"))
      (node (ref "M4") (pin "4") (pinfunction "4_4") (pintype "passive"))
      (node (ref "MASTER") (pin "D23") (pinfunction "D23_D23") (pintype "bidirectional"))
      (node (ref "PULL_MASTER1") (pin "3") (pinfunction "3_3") (pintype "passive"))
    )
    (net (code "34") (name "/D24") (class "Default")
      (node (ref "M4") (pin "5") (pinfunction "5_5") (pintype "passive"))
      (node (ref "MASTER") (pin "D24") (pinfunction "D24_D24") (pintype "bidirectional"))
      (node (ref "P_COMM") (pin "6") (pinfunction "6_6") (pintype "passive"))
    )
    (net (code "35") (name "/D25") (class "Default")
      (node (ref "M4") (pin "6") (pinfunction "6_6") (pintype "passive"))
      (node (ref "MASTER") (pin "D25") (pinfunction "D25_D25") (pintype "bidirectional"))
    )
    (net (code "36") (name "/D26") (class "Default")
      (node (ref "M4") (pin "7") (pinfunction "7_7") (pintype "passive"))
      (node (ref "MASTER") (pin "D26") (pinfunction "D26_D26") (pintype "bidirectional"))
      (node (ref "ULN_2003") (pin "1") (pinfunction "1_1") (pintype "passive"))
    )
    (net (code "37") (name "/D27") (class "Default")
      (node (ref "M4") (pin "8") (pinfunction "8_8") (pintype "passive"))
      (node (ref "MASTER") (pin "D27") (pinfunction "D27_D27") (pintype "bidirectional"))
      (node (ref "ULN_2003") (pin "2") (pinfunction "2_2") (pintype "passive"))
    )
    (net (code "38") (name "/D28") (class "Default")
      (node (ref "M4") (pin "9") (pinfunction "9_9") (pintype "passive"))
      (node (ref "MASTER") (pin "D28") (pinfunction "D28_D28") (pintype "bidirectional"))
      (node (ref "ULN_2003") (pin "3") (pinfunction "3_3") (pintype "passive"))
    )
    (net (code "39") (name "/D29") (class "Default")
      (node (ref "M4") (pin "10") (pinfunction "10_10") (pintype "passive"))
      (node (ref "MASTER") (pin "D29") (pinfunction "D29_D29") (pintype "bidirectional"))
      (node (ref "ULN_2003") (pin "4") (pinfunction "4_4") (pintype "passive"))
    )
    (net (code "40") (name "/D30") (class "Default")
      (node (ref "M4") (pin "11") (pinfunction "11_11") (pintype "passive"))
      (node (ref "MASTER") (pin "D30") (pinfunction "D30_D30") (pintype "bidirectional"))
      (node (ref "ULN_2003") (pin "5") (pinfunction "5_5") (pintype "passive"))
    )
    (net (code "41") (name "/D31") (class "Default")
      (node (ref "M4") (pin "12") (pinfunction "12_12") (pintype "passive"))
      (node (ref "MASTER") (pin "D31") (pinfunction "D31_D31") (pintype "bidirectional"))
      (node (ref "SWITCH1") (pin "1") (pinfunction "1_1") (pintype "bidirectional"))
    )
    (net (code "42") (name "/D32") (class "Default")
      (node (ref "M4") (pin "13") (pinfunction "13_13") (pintype "passive"))
      (node (ref "MASTER") (pin "D32") (pinfunction "D32_D32") (pintype "bidirectional"))
      (node (ref "SWITCH1") (pin "2") (pinfunction "2_2") (pintype "bidirectional"))
    )
    (net (code "43") (name "/D33") (class "Default")
      (node (ref "M4") (pin "14") (pinfunction "14_14") (pintype "passive"))
      (node (ref "MASTER") (pin "D33") (pinfunction "D33_D33") (pintype "bidirectional"))
      (node (ref "SWITCH2") (pin "1") (pinfunction "1_1") (pintype "bidirectional"))
    )
    (net (code "44") (name "/D34") (class "Default")
      (node (ref "M4") (pin "15") (pinfunction "15_15") (pintype "passive"))
      (node (ref "MASTER") (pin "D34") (pinfunction "D34_D34") (pintype "bidirectional"))
      (node (ref "P_COMM") (pin "4") (pinfunction "4_4") (pintype "passive"))
      (node (ref "SWITCH2") (pin "2") (pinfunction "2_2") (pintype "bidirectional"))
    )
    (net (code "45") (name "/D35") (class "Default")
      (node (ref "M4") (pin "16") (pinfunction "16_16") (pintype "passive"))
      (node (ref "MASTER") (pin "D35") (pinfunction "D35_D35") (pintype "bidirectional"))
      (node (ref "P_COMM") (pin "1") (pinfunction "1_1") (pintype "passive"))
    )
    (net (code "46") (name "/D36") (class "Default")
      (node (ref "M4") (pin "17") (pinfunction "17_17") (pintype "passive"))
      (node (ref "MASTER") (pin "D36") (pinfunction "D36_D36") (pintype "bidirectional"))
    )
    (net (code "47") (name "/D38") (class "Default")
      (node (ref "M4") (pin "19") (pinfunction "19_19") (pintype "passive"))
      (node (ref "MASTER") (pin "D38") (pinfunction "D38_D38") (pintype "bidirectional"))
      (node (ref "P_COMM") (pin "2") (pinfunction "2_2") (pintype "passive"))
    )
    (net (code "48") (name "/D40") (class "Default")
      (node (ref "M4") (pin "21") (pinfunction "21_21") (pintype "passive"))
      (node (ref "MASTER") (pin "D40") (pinfunction "D40_D40") (pintype "bidirectional"))
    )
    (net (code "49") (name "/D41") (class "Default")
      (node (ref "BUZ1") (pin "2") (pinfunction "2_2") (pintype "passive"))
      (node (ref "M4") (pin "20") (pinfunction "20_20") (pintype "passive"))
      (node (ref "MASTER") (pin "D39") (pinfunction "D39_D39") (pintype "bidirectional"))
    )
    (net (code "50") (name "/D42") (class "Default")
      (node (ref "K1") (pin "S") (pinfunction "S_S") (pintype "passive"))
      (node (ref "M4") (pin "23") (pinfunction "23_23") (pintype "passive"))
      (node (ref "MASTER") (pin "D42") (pinfunction "D42_D42") (pintype "bidirectional"))
    )
    (net (code "51") (name "/D44") (class "Default")
      (node (ref "ENC_MASTER4") (pin "2") (pinfunction "2_2") (pintype "bidirectional"))
      (node (ref "M4") (pin "25") (pinfunction "25_25") (pintype "passive"))
      (node (ref "MASTER") (pin "D44") (pinfunction "D44_D44") (pintype "bidirectional"))
      (node (ref "PULL_MASTER2") (pin "5") (pinfunction "5_5") (pintype "passive"))
    )
    (net (code "52") (name "/D45") (class "Default")
      (node (ref "M4") (pin "24") (pinfunction "24_24") (pintype "passive"))
      (node (ref "MASTER") (pin "D43") (pinfunction "D43_D43") (pintype "bidirectional"))
      (node (ref "P_COMM") (pin "3") (pinfunction "3_3") (pintype "passive"))
    )
    (net (code "53") (name "/D46") (class "Default")
      (node (ref "M4") (pin "27") (pinfunction "27_27") (pintype "passive"))
      (node (ref "MASTER") (pin "D46") (pinfunction "D46_D46") (pintype "bidirectional"))
    )
    (net (code "54") (name "/D47") (class "Default")
      (node (ref "M4") (pin "26") (pinfunction "26_26") (pintype "passive"))
      (node (ref "MASTER") (pin "D45") (pinfunction "D45_D45") (pintype "bidirectional"))
      (node (ref "P_COMM") (pin "5") (pinfunction "5_5") (pintype "passive"))
    )
    (net (code "55") (name "/D48") (class "Default")
      (node (ref "M4") (pin "29") (pinfunction "29_29") (pintype "passive"))
      (node (ref "MASTER") (pin "D48") (pinfunction "D48_D48") (pintype "bidirectional"))
    )
    (net (code "56") (name "/D49") (class "Default")
      (node (ref "M4") (pin "28") (pinfunction "28_28") (pintype "passive"))
      (node (ref "MASTER") (pin "D47") (pinfunction "D47_D47") (pintype "bidirectional"))
      (node (ref "P_COMM") (pin "7") (pinfunction "7_7") (pintype "passive"))
    )
    (net (code "57") (name "/D50") (class "Default")
      (node (ref "M4") (pin "31") (pinfunction "31_31") (pintype "passive"))
      (node (ref "M8") (pin "7") (pinfunction "MISO_7") (pintype "bidirectional"))
      (node (ref "MASTER") (pin "D50") (pinfunction "D50_D50") (pintype "bidirectional"))
    )
    (net (code "58") (name "/D51") (class "Default")
      (node (ref "M4") (pin "30") (pinfunction "30_30") (pintype "passive"))
      (node (ref "M8") (pin "6") (pinfunction "MOSI_6") (pintype "bidirectional"))
      (node (ref "MASTER") (pin "D49") (pinfunction "D49_D49") (pintype "bidirectional"))
    )
    (net (code "59") (name "/D52") (class "Default")
      (node (ref "M4") (pin "33") (pinfunction "33_33") (pintype "passive"))
      (node (ref "M8") (pin "5") (pinfunction "SCK_5") (pintype "bidirectional"))
      (node (ref "MASTER") (pin "D52") (pinfunction "D52_D52") (pintype "bidirectional"))
    )
    (net (code "60") (name "/D53") (class "Default")
      (node (ref "ENC_MASTER3") (pin "2") (pinfunction "2_2") (pintype "bidirectional"))
      (node (ref "M4") (pin "32") (pinfunction "32_32") (pintype "passive"))
      (node (ref "MASTER") (pin "D51") (pinfunction "D51_D51") (pintype "bidirectional"))
      (node (ref "PULL_MASTER2") (pin "3") (pinfunction "3_3") (pintype "passive"))
    )
    (net (code "61") (name "/GND_J") (class "Default")
      (node (ref "SWITCH") (pin "2") (pinfunction "2_2") (pintype "bidirectional"))
      (node (ref "U$35") (pin "1") (pinfunction "1_1") (pintype "bidirectional"))
    )
    (net (code "62") (name "/O1") (class "Default")
      (node (ref "D14") (pin "K") (pinfunction "C_K") (pintype "passive"))
      (node (ref "PROX_RES") (pin "2") (pinfunction "2_2") (pintype "passive"))
    )
    (net (code "63") (name "/O2") (class "Default")
      (node (ref "D1") (pin "K") (pinfunction "C_K") (pintype "passive"))
      (node (ref "PROX_RES") (pin "3") (pinfunction "3_3") (pintype "passive"))
    )
    (net (code "64") (name "/O3") (class "Default")
      (node (ref "D2") (pin "K") (pinfunction "C_K") (pintype "passive"))
      (node (ref "PROX_RES") (pin "4") (pinfunction "4_4") (pintype "passive"))
    )
    (net (code "65") (name "/O4") (class "Default")
      (node (ref "D3") (pin "K") (pinfunction "C_K") (pintype "passive"))
      (node (ref "PROX_RES") (pin "5") (pinfunction "5_5") (pintype "passive"))
    )
    (net (code "66") (name "/OUTPUT1") (class "Default")
      (node (ref "LM358") (pin "1") (pinfunction "1_1") (pintype "passive"))
      (node (ref "LM358") (pin "2") (pinfunction "2_2") (pintype "passive"))
      (node (ref "PPR1") (pin "1") (pinfunction "1_1") (pintype "passive"))
    )
    (net (code "67") (name "/OUTPUT2") (class "Default")
      (node (ref "LM358") (pin "6") (pinfunction "6_6") (pintype "passive"))
      (node (ref "LM358") (pin "7") (pinfunction "7_7") (pintype "passive"))
      (node (ref "PPR2") (pin "1") (pinfunction "1_1") (pintype "passive"))
    )
    (net (code "68") (name "/PROX1") (class "Default")
      (node (ref "P1") (pin "2") (pinfunction "2_2") (pintype "bidirectional"))
      (node (ref "U$23") (pin "1") (pinfunction "VIN_1") (pintype "bidirectional"))
    )
    (net (code "69") (name "/PROX2") (class "Default")
      (node (ref "P2") (pin "2") (pinfunction "2_2") (pintype "bidirectional"))
      (node (ref "U$24") (pin "1") (pinfunction "VIN_1") (pintype "bidirectional"))
    )
    (net (code "70") (name "/PROX3") (class "Default")
      (node (ref "P3") (pin "2") (pinfunction "2_2") (pintype "bidirectional"))
      (node (ref "U$25") (pin "1") (pinfunction "VIN_1") (pintype "bidirectional"))
    )
    (net (code "71") (name "/PROX4") (class "Default")
      (node (ref "P4") (pin "2") (pinfunction "2_2") (pintype "bidirectional"))
      (node (ref "U$26") (pin "1") (pinfunction "VIN_1") (pintype "bidirectional"))
    )
    (net (code "72") (name "/RX0") (class "Default")
      (node (ref "M2") (pin "1") (pinfunction "1_1") (pintype "passive"))
      (node (ref "MASTER") (pin "RX0") (pinfunction "RX0_RX0") (pintype "bidirectional"))
      (node (ref "U$4") (pin "RX0") (pinfunction "RX_RX0") (pintype "bidirectional"))
    )
    (net (code "73") (name "/RX1") (class "Default")
      (node (ref "M3") (pin "3") (pinfunction "3_3") (pintype "passive"))
      (node (ref "MASTER") (pin "RX1") (pinfunction "RX1_RX1") (pintype "bidirectional"))
      (node (ref "S_COMM") (pin "2") (pinfunction "2_2") (pintype "passive"))
    )
    (net (code "74") (name "/RX2") (class "Default")
      (node (ref "M3") (pin "5") (pinfunction "5_5") (pintype "passive"))
      (node (ref "MASTER") (pin "RX2") (pinfunction "RX2_RX2") (pintype "bidirectional"))
      (node (ref "ODRIVE2") (pin "2") (pinfunction "2_2") (pintype "passive"))
    )
    (net (code "75") (name "/RX3") (class "Default")
      (node (ref "M3") (pin "7") (pinfunction "7_7") (pintype "passive"))
      (node (ref "MASTER") (pin "RX3") (pinfunction "RX3_RX3") (pintype "bidirectional"))
      (node (ref "ODRIVE1") (pin "2") (pinfunction "2_2") (pintype "passive"))
    )
    (net (code "76") (name "/S-3V3") (class "Default")
      (node (ref "S7") (pin "4") (pinfunction "4_4") (pintype "passive"))
      (node (ref "SLAVE") (pin "3V3") (pinfunction "3V3_3V3") (pintype "bidirectional"))
    )
    (net (code "77") (name "/S-A0") (class "Default")
      (node (ref "S6") (pin "1") (pinfunction "1_1") (pintype "passive"))
      (node (ref "SLAVE") (pin "A0") (pinfunction "A0_A0") (pintype "bidirectional"))
    )
    (net (code "78") (name "/S-A1") (class "Default")
      (node (ref "S6") (pin "2") (pinfunction "2_2") (pintype "passive"))
      (node (ref "SLAVE") (pin "A1") (pinfunction "A1_A1") (pintype "bidirectional"))
    )
    (net (code "79") (name "/S-A2") (class "Default")
      (node (ref "S6") (pin "3") (pinfunction "3_3") (pintype "passive"))
      (node (ref "SLAVE") (pin "A2") (pinfunction "A2_A2") (pintype "bidirectional"))
    )
    (net (code "80") (name "/S-A3") (class "Default")
      (node (ref "S6") (pin "4") (pinfunction "4_4") (pintype "passive"))
      (node (ref "SLAVE") (pin "A3") (pinfunction "A3_A3") (pintype "bidirectional"))
    )
    (net (code "81") (name "/S-A4") (class "Default")
      (node (ref "S6") (pin "5") (pinfunction "5_5") (pintype "passive"))
      (node (ref "SLAVE") (pin "A4") (pinfunction "A4_A4") (pintype "bidirectional"))
    )
    (net (code "82") (name "/S-A5") (class "Default")
      (node (ref "S6") (pin "6") (pinfunction "6_6") (pintype "passive"))
      (node (ref "SLAVE") (pin "A5") (pinfunction "A5_A5") (pintype "bidirectional"))
    )
    (net (code "83") (name "/S-A6") (class "Default")
      (node (ref "S6") (pin "7") (pinfunction "7_7") (pintype "passive"))
      (node (ref "SLAVE") (pin "A6") (pinfunction "A6_A6") (pintype "bidirectional"))
    )
    (net (code "84") (name "/S-A7") (class "Default")
      (node (ref "S6") (pin "8") (pinfunction "8_8") (pintype "passive"))
      (node (ref "SLAVE") (pin "A7") (pinfunction "A7_A7") (pintype "bidirectional"))
    )
    (net (code "85") (name "/S-A8") (class "Default")
      (node (ref "ODRIVE4") (pin "3") (pinfunction "3_3") (pintype "passive"))
      (node (ref "S5") (pin "1") (pinfunction "1_1") (pintype "passive"))
      (node (ref "SLAVE") (pin "A8") (pinfunction "A8_A8") (pintype "bidirectional"))
    )
    (net (code "86") (name "/S-A9") (class "Default")
      (node (ref "ODRIVE4") (pin "2") (pinfunction "2_2") (pintype "passive"))
      (node (ref "S5") (pin "2") (pinfunction "2_2") (pintype "passive"))
      (node (ref "SLAVE") (pin "A9") (pinfunction "A9_A9") (pintype "bidirectional"))
    )
    (net (code "87") (name "/S-A10") (class "Default")
      (node (ref "ODRIVE3") (pin "3") (pinfunction "3_3") (pintype "passive"))
      (node (ref "S5") (pin "3") (pinfunction "3_3") (pintype "passive"))
      (node (ref "SLAVE") (pin "A10") (pinfunction "A10_A10") (pintype "bidirectional"))
    )
    (net (code "88") (name "/S-A11") (class "Default")
      (node (ref "ODRIVE3") (pin "2") (pinfunction "2_2") (pintype "passive"))
      (node (ref "S5") (pin "4") (pinfunction "4_4") (pintype "passive"))
      (node (ref "SLAVE") (pin "A11") (pinfunction "A11_A11") (pintype "bidirectional"))
    )
    (net (code "89") (name "/S-A12") (class "Default")
      (node (ref "S5") (pin "5") (pinfunction "5_5") (pintype "passive"))
      (node (ref "SLAVE") (pin "A12") (pinfunction "A12_A12") (pintype "bidirectional"))
    )
    (net (code "90") (name "/S-A13") (class "Default")
      (node (ref "S5") (pin "6") (pinfunction "6_6") (pintype "passive"))
      (node (ref "SLAVE") (pin "A13") (pinfunction "A13_A13") (pintype "bidirectional"))
    )
    (net (code "91") (name "/S-A14") (class "Default")
      (node (ref "S5") (pin "7") (pinfunction "7_7") (pintype "passive"))
      (node (ref "SLAVE") (pin "A14") (pinfunction "A14_A14") (pintype "bidirectional"))
    )
    (net (code "92") (name "/S-A15") (class "Default")
      (node (ref "S5") (pin "8") (pinfunction "8_8") (pintype "passive"))
      (node (ref "SLAVE") (pin "A15") (pinfunction "A15_A15") (pintype "bidirectional"))
    )
    (net (code "93") (name "/S-AREF") (class "Default")
      (node (ref "S1") (pin "8") (pinfunction "8_8") (pintype "passive"))
      (node (ref "SLAVE") (pin "AREF") (pinfunction "AREF_AREF") (pintype "bidirectional"))
    )
    (net (code "94") (name "/S-D2") (class "Default")
      (node (ref "ENC_SLAVE1") (pin "3") (pinfunction "3_3") (pintype "bidirectional"))
      (node (ref "S2") (pin "3") (pinfunction "3_3") (pintype "passive"))
      (node (ref "SLAVE") (pin "D2") (pinfunction "D2_D2") (pintype "bidirectional"))
      (node (ref "S_ENC_PULL1") (pin "4") (pinfunction "4_4") (pintype "passive"))
    )
    (net (code "95") (name "/S-D3") (class "Default")
      (node (ref "ENC_SLAVE2") (pin "3") (pinfunction "3_3") (pintype "bidirectional"))
      (node (ref "S2") (pin "4") (pinfunction "4_4") (pintype "passive"))
      (node (ref "SLAVE") (pin "D3") (pinfunction "D3_D3") (pintype "bidirectional"))
      (node (ref "S_ENC_PULL1") (pin "2") (pinfunction "2_2") (pintype "passive"))
    )
    (net (code "96") (name "/S-D4") (class "Default")
      (node (ref "S2") (pin "5") (pinfunction "5_5") (pintype "passive"))
      (node (ref "SLAVE") (pin "D4") (pinfunction "D4_D4") (pintype "bidirectional"))
    )
    (net (code "97") (name "/S-D5") (class "Default")
      (node (ref "ENC_SLAVE3") (pin "3") (pinfunction "3_3") (pintype "bidirectional"))
      (node (ref "PULL_SLAVE3") (pin "2") (pinfunction "2_2") (pintype "passive"))
      (node (ref "S2") (pin "6") (pinfunction "6_6") (pintype "passive"))
      (node (ref "SLAVE") (pin "D5") (pinfunction "D5_D5") (pintype "bidirectional"))
    )
    (net (code "98") (name "/S-D6") (class "Default")
      (node (ref "S2") (pin "7") (pinfunction "7_7") (pintype "passive"))
      (node (ref "SLAVE") (pin "D6") (pinfunction "D6_D6") (pintype "bidirectional"))
    )
    (net (code "99") (name "/S-D7") (class "Default")
      (node (ref "S2") (pin "8") (pinfunction "8_8") (pintype "passive"))
      (node (ref "SLAVE") (pin "D7") (pinfunction "D7_D7") (pintype "bidirectional"))
    )
    (net (code "100") (name "/S-D8") (class "Default")
      (node (ref "CYTRN1") (pin "3") (pinfunction "3_3") (pintype "bidirectional"))
      (node (ref "S1") (pin "1") (pinfunction "1_1") (pintype "passive"))
      (node (ref "SLAVE") (pin "D8") (pinfunction "D8_D8") (pintype "bidirectional"))
    )
    (net (code "101") (name "/S-D9") (class "Default")
      (node (ref "CYTRN2") (pin "3") (pinfunction "3_3") (pintype "bidirectional"))
      (node (ref "S1") (pin "2") (pinfunction "2_2") (pintype "passive"))
      (node (ref "SLAVE") (pin "D9") (pinfunction "D9_D9") (pintype "bidirectional"))
    )
    (net (code "102") (name "/S-D10") (class "Default")
      (node (ref "S1") (pin "3") (pinfunction "3_3") (pintype "passive"))
      (node (ref "SLAVE") (pin "D10") (pinfunction "D10_D10") (pintype "bidirectional"))
    )
    (net (code "103") (name "/S-D11") (class "Default")
      (node (ref "S1") (pin "4") (pinfunction "4_4") (pintype "passive"))
      (node (ref "SLAVE") (pin "D11") (pinfunction "D11_D11") (pintype "bidirectional"))
    )
    (net (code "104") (name "/S-D12") (class "Default")
      (node (ref "ENC_SLAVE4") (pin "3") (pinfunction "3_3") (pintype "bidirectional"))
      (node (ref "PULL_SLAVE3") (pin "4") (pinfunction "4_4") (pintype "passive"))
      (node (ref "S1") (pin "5") (pinfunction "5_5") (pintype "passive"))
      (node (ref "SLAVE") (pin "D12") (pinfunction "D12_D12") (pintype "bidirectional"))
    )
    (net (code "105") (name "/S-D13") (class "Default")
      (node (ref "S1") (pin "6") (pinfunction "6_6") (pintype "passive"))
      (node (ref "SLAVE") (pin "D13") (pinfunction "D13_D13") (pintype "bidirectional"))
    )
    (net (code "106") (name "/S-D22") (class "Default")
      (node (ref "ENC_SLAVE1") (pin "2") (pinfunction "2_2") (pintype "bidirectional"))
      (node (ref "S-4") (pin "3") (pinfunction "3_3") (pintype "passive"))
      (node (ref "SLAVE") (pin "D22") (pinfunction "D22_D22") (pintype "bidirectional"))
      (node (ref "S_ENC_PULL1") (pin "5") (pinfunction "5_5") (pintype "passive"))
    )
    (net (code "107") (name "/S-D23") (class "Default")
      (node (ref "ENC_SLAVE2") (pin "2") (pinfunction "2_2") (pintype "bidirectional"))
      (node (ref "S-4") (pin "4") (pinfunction "4_4") (pintype "passive"))
      (node (ref "SLAVE") (pin "D23") (pinfunction "D23_D23") (pintype "bidirectional"))
      (node (ref "S_ENC_PULL1") (pin "3") (pinfunction "3_3") (pintype "passive"))
    )
    (net (code "108") (name "/S-D24") (class "Default")
      (node (ref "D2") (pin "A") (pinfunction "A_A") (pintype "passive"))
      (node (ref "S-4") (pin "5") (pinfunction "5_5") (pintype "passive"))
      (node (ref "SLAVE") (pin "D24") (pinfunction "D24_D24") (pintype "bidirectional"))
      (node (ref "U$25") (pin "3") (pinfunction "VO_3") (pintype "bidirectional"))
    )
    (net (code "109") (name "/S-D25") (class "Default")
      (node (ref "D3") (pin "A") (pinfunction "A_A") (pintype "passive"))
      (node (ref "S-4") (pin "6") (pinfunction "6_6") (pintype "passive"))
      (node (ref "SLAVE") (pin "D25") (pinfunction "D25_D25") (pintype "bidirectional"))
      (node (ref "U$26") (pin "3") (pinfunction "VO_3") (pintype "bidirectional"))
    )
    (net (code "110") (name "/S-D26") (class "Default")
      (node (ref "CYTRN1") (pin "2") (pinfunction "2_2") (pintype "bidirectional"))
      (node (ref "D14") (pin "A") (pinfunction "A_A") (pintype "passive"))
      (node (ref "P_COMM") (pin "16") (pinfunction "16_16") (pintype "passive"))
      (node (ref "S-4") (pin "7") (pinfunction "7_7") (pintype "passive"))
      (node (ref "SLAVE") (pin "D26") (pinfunction "D26_D26") (pintype "bidirectional"))
      (node (ref "U$23") (pin "3") (pinfunction "VO_3") (pintype "bidirectional"))
    )
    (net (code "111") (name "/S-D27") (class "Default")
      (node (ref "CYTRN2") (pin "2") (pinfunction "2_2") (pintype "bidirectional"))
      (node (ref "D1") (pin "A") (pinfunction "A_A") (pintype "passive"))
      (node (ref "P_COMM") (pin "15") (pinfunction "15_15") (pintype "passive"))
      (node (ref "S-4") (pin "8") (pinfunction "8_8") (pintype "passive"))
      (node (ref "SLAVE") (pin "D27") (pinfunction "D27_D27") (pintype "bidirectional"))
      (node (ref "U$24") (pin "3") (pinfunction "VO_3") (pintype "bidirectional"))
    )
    (net (code "112") (name "/S-D28") (class "Default")
      (node (ref "P_COMM") (pin "12") (pinfunction "12_12") (pintype "passive"))
      (node (ref "S-4") (pin "9") (pinfunction "9_9") (pintype "passive"))
      (node (ref "SLAVE") (pin "D28") (pinfunction "D28_D28") (pintype "bidirectional"))
    )
    (net (code "113") (name "/S-D29") (class "Default")
      (node (ref "P_COMM") (pin "11") (pinfunction "11_11") (pintype "passive"))
      (node (ref "S-4") (pin "10") (pinfunction "10_10") (pintype "passive"))
      (node (ref "SLAVE") (pin "D29") (pinfunction "D29_D29") (pintype "bidirectional"))
    )
    (net (code "114") (name "/S-D30") (class "Default")
      (node (ref "P_COMM") (pin "10") (pinfunction "10_10") (pintype "passive"))
      (node (ref "S-4") (pin "11") (pinfunction "11_11") (pintype "passive"))
      (node (ref "SLAVE") (pin "D30") (pinfunction "D30_D30") (pintype "bidirectional"))
    )
    (net (code "115") (name "/S-D31") (class "Default")
      (node (ref "S-4") (pin "12") (pinfunction "12_12") (pintype "passive"))
      (node (ref "SLAVE") (pin "D31") (pinfunction "D31_D31") (pintype "bidirectional"))
    )
    (net (code "116") (name "/S-D32") (class "Default")
      (node (ref "S-4") (pin "13") (pinfunction "13_13") (pintype "passive"))
      (node (ref "SLAVE") (pin "D32") (pinfunction "D32_D32") (pintype "bidirectional"))
    )
    (net (code "117") (name "/S-D33") (class "Default")
      (node (ref "S-4") (pin "14") (pinfunction "14_14") (pintype "passive"))
      (node (ref "SLAVE") (pin "D33") (pinfunction "D33_D33") (pintype "bidirectional"))
    )
    (net (code "118") (name "/S-D34") (class "Default")
      (node (ref "S-4") (pin "15") (pinfunction "15_15") (pintype "passive"))
      (node (ref "SLAVE") (pin "D34") (pinfunction "D34_D34") (pintype "bidirectional"))
    )
    (net (code "119") (name "/S-D35") (class "Default")
      (node (ref "S-4") (pin "16") (pinfunction "16_16") (pintype "passive"))
      (node (ref "SLAVE") (pin "D35") (pinfunction "D35_D35") (pintype "bidirectional"))
    )
    (net (code "120") (name "/S-D36") (class "Default")
      (node (ref "S-4") (pin "17") (pinfunction "17_17") (pintype "passive"))
      (node (ref "SLAVE") (pin "D36") (pinfunction "D36_D36") (pintype "bidirectional"))
    )
    (net (code "121") (name "/S-D37") (class "Default")
      (node (ref "S-4") (pin "18") (pinfunction "18_18") (pintype "passive"))
      (node (ref "SLAVE") (pin "D37") (pinfunction "D37_D37") (pintype "bidirectional"))
    )
    (net (code "122") (name "/S-D38") (class "Default")
      (node (ref "LIMIT_SWITCH1") (pin "1") (pinfunction "1_1") (pintype "bidirectional"))
      (node (ref "S-4") (pin "19") (pinfunction "19_19") (pintype "passive"))
      (node (ref "SLAVE") (pin "D38") (pinfunction "D38_D38") (pintype "bidirectional"))
    )
    (net (code "123") (name "/S-D39") (class "Default")
      (node (ref "LIMIT_SWITCH1") (pin "2") (pinfunction "2_2") (pintype "bidirectional"))
      (node (ref "S-4") (pin "20") (pinfunction "20_20") (pintype "passive"))
      (node (ref "SLAVE") (pin "D39") (pinfunction "D39_D39") (pintype "bidirectional"))
    )
    (net (code "124") (name "/S-D40") (class "Default")
      (node (ref "LIMIT_SWITCH2") (pin "1") (pinfunction "1_1") (pintype "bidirectional"))
      (node (ref "S-4") (pin "21") (pinfunction "21_21") (pintype "passive"))
      (node (ref "SLAVE") (pin "D40") (pinfunction "D40_D40") (pintype "bidirectional"))
    )
    (net (code "125") (name "/S-D41") (class "Default")
      (node (ref "BUZ2") (pin "2") (pinfunction "2_2") (pintype "passive"))
      (node (ref "LIMIT_SWITCH2") (pin "2") (pinfunction "2_2") (pintype "bidirectional"))
      (node (ref "S-4") (pin "22") (pinfunction "22_22") (pintype "passive"))
      (node (ref "SLAVE") (pin "D41") (pinfunction "D41_D41") (pintype "bidirectional"))
    )
    (net (code "126") (name "/S-D42") (class "Default")
      (node (ref "R8") (pin "2") (pinfunction "2_2") (pintype "passive"))
      (node (ref "S-4") (pin "23") (pinfunction "23_23") (pintype "passive"))
      (node (ref "SLAVE") (pin "D42") (pinfunction "D42_D42") (pintype "bidirectional"))
    )
    (net (code "127") (name "/S-D43") (class "Default")
      (node (ref "R9") (pin "2") (pinfunction "2_2") (pintype "passive"))
      (node (ref "S-4") (pin "24") (pinfunction "24_24") (pintype "passive"))
      (node (ref "SLAVE") (pin "D43") (pinfunction "D43_D43") (pintype "bidirectional"))
    )
    (net (code "128") (name "/S-D44") (class "Default")
      (node (ref "ENC_SLAVE4") (pin "2") (pinfunction "2_2") (pintype "bidirectional"))
      (node (ref "PULL_SLAVE3") (pin "5") (pinfunction "5_5") (pintype "passive"))
      (node (ref "S-4") (pin "25") (pinfunction "25_25") (pintype "passive"))
      (node (ref "SLAVE") (pin "D44") (pinfunction "D44_D44") (pintype "bidirectional"))
    )
    (net (code "129") (name "/S-D45") (class "Default")
      (node (ref "R10") (pin "2") (pinfunction "2_2") (pintype "passive"))
      (node (ref "S-4") (pin "26") (pinfunction "26_26") (pintype "passive"))
      (node (ref "SLAVE") (pin "D45") (pinfunction "D45_D45") (pintype "bidirectional"))
    )
    (net (code "130") (name "/S-D46") (class "Default")
      (node (ref "S-4") (pin "27") (pinfunction "27_27") (pintype "passive"))
      (node (ref "SLAVE") (pin "D46") (pinfunction "D46_D46") (pintype "bidirectional"))
    )
    (net (code "131") (name "/S-D47") (class "Default")
      (node (ref "S-4") (pin "28") (pinfunction "28_28") (pintype "passive"))
      (node (ref "SLAVE") (pin "D47") (pinfunction "D47_D47") (pintype "bidirectional"))
    )
    (net (code "132") (name "/S-D48") (class "Default")
      (node (ref "P_COMM") (pin "9") (pinfunction "9_9") (pintype "passive"))
      (node (ref "S-4") (pin "29") (pinfunction "29_29") (pintype "passive"))
      (node (ref "SLAVE") (pin "D48") (pinfunction "D48_D48") (pintype "bidirectional"))
    )
    (net (code "133") (name "/S-D49") (class "Default")
      (node (ref "S-4") (pin "30") (pinfunction "30_30") (pintype "passive"))
      (node (ref "SLAVE") (pin "D49") (pinfunction "D49_D49") (pintype "bidirectional"))
    )
    (net (code "134") (name "/S-D50") (class "Default")
      (node (ref "S-4") (pin "31") (pinfunction "31_31") (pintype "passive"))
      (node (ref "SLAVE") (pin "D50") (pinfunction "D50_D50") (pintype "bidirectional"))
    )
    (net (code "135") (name "/S-D51") (class "Default")
      (node (ref "P_COMM") (pin "13") (pinfunction "13_13") (pintype "passive"))
      (node (ref "S-4") (pin "32") (pinfunction "32_32") (pintype "passive"))
      (node (ref "SLAVE") (pin "D51") (pinfunction "D51_D51") (pintype "bidirectional"))
    )
    (net (code "136") (name "/S-D52") (class "Default")
      (node (ref "P_COMM") (pin "14") (pinfunction "14_14") (pintype "passive"))
      (node (ref "S-4") (pin "33") (pinfunction "33_33") (pintype "passive"))
      (node (ref "SLAVE") (pin "D52") (pinfunction "D52_D52") (pintype "bidirectional"))
    )
    (net (code "137") (name "/S-D53") (class "Default")
      (node (ref "ENC_SLAVE3") (pin "2") (pinfunction "2_2") (pintype "bidirectional"))
      (node (ref "PULL_SLAVE3") (pin "3") (pinfunction "3_3") (pintype "passive"))
      (node (ref "R1") (pin "2") (pinfunction "2_2") (pintype "passive"))
      (node (ref "S-4") (pin "34") (pinfunction "34_34") (pintype "passive"))
      (node (ref "SLAVE") (pin "D53") (pinfunction "D53_D53") (pintype "bidirectional"))
    )
    (net (code "138") (name "/S-RX0") (class "Default")
      (node (ref "S2") (pin "1") (pinfunction "1_1") (pintype "passive"))
      (node (ref "SLAVE") (pin "RX0") (pinfunction "RX0_RX0") (pintype "bidirectional"))
    )
    (net (code "139") (name "/S-RX1") (class "Default")
      (node (ref "S-3") (pin "3") (pinfunction "3_3") (pintype "passive"))
      (node (ref "SLAVE") (pin "RX1") (pinfunction "RX1_RX1") (pintype "bidirectional"))
      (node (ref "S_COMM") (pin "4") (pinfunction "4_4") (pintype "passive"))
    )
    (net (code "140") (name "/S-RX2") (class "Default")
      (node (ref "S-3") (pin "5") (pinfunction "5_5") (pintype "passive"))
      (node (ref "SLAVE") (pin "RX2") (pinfunction "RX2_RX2") (pintype "bidirectional"))
    )
    (net (code "141") (name "/S-RX3") (class "Default")
      (node (ref "S-3") (pin "7") (pinfunction "7_7") (pintype "passive"))
      (node (ref "SLAVE") (pin "RX3") (pinfunction "RX3_RX3") (pintype "bidirectional"))
    )
    (net (code "142") (name "/S-TX0") (class "Default")
      (node (ref "S2") (pin "2") (pinfunction "2_2") (pintype "passive"))
      (node (ref "SABER2") (pin "2") (pinfunction "2_2") (pintype "passive"))
      (node (ref "SLAVE") (pin "TX0") (pinfunction "TX0_TX0") (pintype "bidirectional"))
    )
    (net (code "143") (name "/S-TX1") (class "Default")
      (node (ref "S-3") (pin "4") (pinfunction "4_4") (pintype "passive"))
      (node (ref "SLAVE") (pin "TX1") (pinfunction "TX1_TX1") (pintype "bidirectional"))
      (node (ref "S_COMM") (pin "3") (pinfunction "3_3") (pintype "passive"))
    )
    (net (code "144") (name "/S-TX2") (class "Default")
      (node (ref "S-3") (pin "6") (pinfunction "6_6") (pintype "passive"))
      (node (ref "SABER3") (pin "2") (pinfunction "2_2") (pintype "passive"))
      (node (ref "SLAVE") (pin "TX2") (pinfunction "TX2_TX2") (pintype "bidirectional"))
    )
    (net (code "145") (name "/S-TX3") (class "Default")
      (node (ref "S-3") (pin "8") (pinfunction "8_8") (pintype "passive"))
      (node (ref "SABER4") (pin "2") (pinfunction "2_2") (pintype "passive"))
      (node (ref "SLAVE") (pin "TX3") (pinfunction "TX3_TX3") (pintype "bidirectional"))
    )
    (net (code "146") (name "/TX0") (class "Default")
      (node (ref "M2") (pin "2") (pinfunction "2_2") (pintype "passive"))
      (node (ref "MASTER") (pin "TX0") (pinfunction "TX0_TX0") (pintype "bidirectional"))
      (node (ref "SABER1") (pin "2") (pinfunction "2_2") (pintype "passive"))
      (node (ref "U$4") (pin "TX0") (pinfunction "TX_TX0") (pintype "bidirectional"))
    )
    (net (code "147") (name "/TX1") (class "Default")
      (node (ref "M3") (pin "4") (pinfunction "4_4") (pintype "passive"))
      (node (ref "MASTER") (pin "TX1") (pinfunction "TX1_TX1") (pintype "bidirectional"))
      (node (ref "S_COMM") (pin "1") (pinfunction "1_1") (pintype "passive"))
    )
    (net (code "148") (name "/TX2") (class "Default")
      (node (ref "M3") (pin "6") (pinfunction "6_6") (pintype "passive"))
      (node (ref "MASTER") (pin "TX2") (pinfunction "TX2_TX2") (pintype "bidirectional"))
      (node (ref "ODRIVE2") (pin "3") (pinfunction "3_3") (pintype "passive"))
    )
    (net (code "149") (name "/TX3") (class "Default")
      (node (ref "M3") (pin "8") (pinfunction "8_8") (pintype "passive"))
      (node (ref "MASTER") (pin "TX3") (pinfunction "TX3_TX3") (pintype "bidirectional"))
      (node (ref "ODRIVE1") (pin "3") (pinfunction "3_3") (pintype "passive"))
    )
    (net (code "150") (name "/U1") (class "Default")
      (node (ref "D10") (pin "K") (pinfunction "C_K") (pintype "passive"))
      (node (ref "ULN2") (pin "1") (pinfunction "1_1") (pintype "bidirectional"))
      (node (ref "ULN_2003") (pin "12") (pinfunction "12_12") (pintype "passive"))
    )
    (net (code "151") (name "/U2") (class "Default")
      (node (ref "D9") (pin "K") (pinfunction "C_K") (pintype "passive"))
      (node (ref "ULN2") (pin "2") (pinfunction "2_2") (pintype "bidirectional"))
      (node (ref "ULN_2003") (pin "13") (pinfunction "13_13") (pintype "passive"))
    )
    (net (code "152") (name "/U3") (class "Default")
      (node (ref "D8") (pin "K") (pinfunction "C_K") (pintype "passive"))
      (node (ref "ULN2") (pin "3") (pinfunction "3_3") (pintype "bidirectional"))
      (node (ref "ULN_2003") (pin "14") (pinfunction "14_14") (pintype "passive"))
    )
    (net (code "153") (name "/U4") (class "Default")
      (node (ref "D7") (pin "K") (pinfunction "C_K") (pintype "passive"))
      (node (ref "ULN1") (pin "1") (pinfunction "1_1") (pintype "bidirectional"))
      (node (ref "ULN_2003") (pin "15") (pinfunction "15_15") (pintype "passive"))
    )
    (net (code "154") (name "/U5") (class "Default")
      (node (ref "D6") (pin "K") (pinfunction "C_K") (pintype "passive"))
      (node (ref "ULN1") (pin "2") (pinfunction "2_2") (pintype "bidirectional"))
      (node (ref "ULN_2003") (pin "16") (pinfunction "16_16") (pintype "passive"))
    )
    (net (code "155") (name "/VIN") (class "Default")
      (node (ref "M7") (pin "8") (pinfunction "8_8") (pintype "passive"))
      (node (ref "MASTER") (pin "VIN") (pinfunction "VIN_VIN") (pintype "bidirectional"))
      (node (ref "S7") (pin "8") (pinfunction "8_8") (pintype "passive"))
      (node (ref "SLAVE") (pin "VIN") (pinfunction "VIN_VIN") (pintype "bidirectional"))
      (node (ref "U$2") (pin "3") (pinfunction "3_3") (pintype "bidirectional"))
      (node (ref "U$4") (pin "VIN") (pinfunction "VIN_VIN") (pintype "bidirectional"))
    )
    (net (code "156") (name "/VREF") (class "Default")
      (node (ref "M7") (pin "2") (pinfunction "2_2") (pintype "passive"))
      (node (ref "MASTER") (pin "IOREF") (pinfunction "IOREF_IOREF") (pintype "bidirectional"))
      (node (ref "U$4") (pin "VREF") (pinfunction "VREF_VREF") (pintype "bidirectional"))
    )
    (net (code "157") (name "5V") (class "Default")
      (node (ref "5V") (pin "3") (pinfunction "3_3") (pintype "passive"))
      (node (ref "5V") (pin "4") (pinfunction "4_4") (pintype "passive"))
      (node (ref "5V_1") (pin "1") (pinfunction "1_1") (pintype "passive"))
      (node (ref "5V_1") (pin "2") (pinfunction "2_2") (pintype "passive"))
      (node (ref "5V_1") (pin "3") (pinfunction "3_3") (pintype "passive"))
      (node (ref "5V_1") (pin "4") (pinfunction "4_4") (pintype "passive"))
      (node (ref "5V_1") (pin "5") (pinfunction "5_5") (pintype "passive"))
      (node (ref "AMS1117_1") (pin "2") (pinfunction "OUT_2") (pintype "bidirectional"))
      (node (ref "AMS1117_2") (pin "2") (pinfunction "OUT_2") (pintype "bidirectional"))
      (node (ref "ENC_MASTER1") (pin "5") (pinfunction "5_5") (pintype "bidirectional"))
      (node (ref "ENC_MASTER2") (pin "5") (pinfunction "5_5") (pintype "bidirectional"))
      (node (ref "ENC_MASTER3") (pin "5") (pinfunction "5_5") (pintype "bidirectional"))
      (node (ref "ENC_MASTER4") (pin "5") (pinfunction "5_5") (pintype "bidirectional"))
      (node (ref "ENC_SLAVE1") (pin "5") (pinfunction "5_5") (pintype "bidirectional"))
      (node (ref "ENC_SLAVE2") (pin "5") (pinfunction "5_5") (pintype "bidirectional"))
      (node (ref "ENC_SLAVE3") (pin "5") (pinfunction "5_5") (pintype "bidirectional"))
      (node (ref "ENC_SLAVE4") (pin "5") (pinfunction "5_5") (pintype "bidirectional"))
      (node (ref "I2C1P_MASTER") (pin "1") (pinfunction "1_1") (pintype "passive"))
      (node (ref "IMU_BLOCK2") (pin "4") (pinfunction "4_4") (pintype "bidirectional"))
      (node (ref "IMU_MASTER") (pin "4") (pinfunction "4_4") (pintype "bidirectional"))
      (node (ref "PULL_MASTER1") (pin "1") (pinfunction "1_1") (pintype "passive"))
      (node (ref "PULL_MASTER2") (pin "1") (pinfunction "1_1") (pintype "passive"))
      (node (ref "PULL_SLAVE3") (pin "1") (pinfunction "1_1") (pintype "passive"))
      (node (ref "SERVO1") (pin "2") (pinfunction "2_2") (pintype "bidirectional"))
      (node (ref "SERVO2") (pin "2") (pinfunction "2_2") (pintype "bidirectional"))
      (node (ref "S_ENC_PULL1") (pin "1") (pinfunction "1_1") (pintype "passive"))
      (node (ref "ULN_PULL") (pin "1") (pinfunction "1_1") (pintype "passive"))
    )
    (net (code "158") (name "5VA") (class "Default")
      (node (ref "5V") (pin "1") (pinfunction "1_1") (pintype "passive"))
      (node (ref "M4") (pin "1") (pinfunction "1_1") (pintype "passive"))
      (node (ref "M4") (pin "2") (pinfunction "2_2") (pintype "passive"))
      (node (ref "M7") (pin "5") (pinfunction "5_5") (pintype "passive"))
      (node (ref "MASTER") (pin "5V") (pinfunction "5V_5V") (pintype "bidirectional"))
      (node (ref "MASTER") (pin "5V1") (pinfunction "5V1_5V1") (pintype "bidirectional"))
      (node (ref "MASTER") (pin "5V2") (pinfunction "5V2_5V2") (pintype "bidirectional"))
      (node (ref "MASTER") (pin "5V3") (pinfunction "5V3_5V3") (pintype "bidirectional"))
      (node (ref "SWITCH") (pin "1") (pinfunction "1_1") (pintype "bidirectional"))
      (node (ref "U$4") (pin "5V") (pinfunction "5V_5V") (pintype "bidirectional"))
      (node (ref "U$4") (pin "5V1") (pinfunction "5V1_5V1") (pintype "bidirectional"))
    )
    (net (code "159") (name "GND") (class "Default")
      (node (ref "AMS1117_1") (pin "3") (pinfunction "GND_3") (pintype "bidirectional"))
      (node (ref "AMS1117_2") (pin "3") (pinfunction "GND_3") (pintype "bidirectional"))
      (node (ref "BUZZER") (pin "-") (pinfunction "2_-") (pintype "passive"))
      (node (ref "C1") (pin "2") (pinfunction "-_2") (pintype "passive"))
      (node (ref "C2") (pin "2") (pinfunction "-_2") (pintype "passive"))
      (node (ref "CYTRN1") (pin "1") (pinfunction "1_1") (pintype "bidirectional"))
      (node (ref "CYTRN2") (pin "1") (pinfunction "1_1") (pintype "bidirectional"))
      (node (ref "ENC_MASTER1") (pin "1") (pinfunction "1_1") (pintype "bidirectional"))
      (node (ref "ENC_MASTER1") (pin "4") (pinfunction "4_4") (pintype "bidirectional"))
      (node (ref "ENC_MASTER2") (pin "1") (pinfunction "1_1") (pintype "bidirectional"))
      (node (ref "ENC_MASTER2") (pin "4") (pinfunction "4_4") (pintype "bidirectional"))
      (node (ref "ENC_MASTER3") (pin "1") (pinfunction "1_1") (pintype "bidirectional"))
      (node (ref "ENC_MASTER3") (pin "4") (pinfunction "4_4") (pintype "bidirectional"))
      (node (ref "ENC_MASTER4") (pin "1") (pinfunction "1_1") (pintype "bidirectional"))
      (node (ref "ENC_MASTER4") (pin "4") (pinfunction "4_4") (pintype "bidirectional"))
      (node (ref "ENC_SLAVE1") (pin "1") (pinfunction "1_1") (pintype "bidirectional"))
      (node (ref "ENC_SLAVE1") (pin "4") (pinfunction "4_4") (pintype "bidirectional"))
      (node (ref "ENC_SLAVE2") (pin "1") (pinfunction "1_1") (pintype "bidirectional"))
      (node (ref "ENC_SLAVE2") (pin "4") (pinfunction "4_4") (pintype "bidirectional"))
      (node (ref "ENC_SLAVE3") (pin "1") (pinfunction "1_1") (pintype "bidirectional"))
      (node (ref "ENC_SLAVE3") (pin "4") (pinfunction "4_4") (pintype "bidirectional"))
      (node (ref "ENC_SLAVE4") (pin "1") (pinfunction "1_1") (pintype "bidirectional"))
      (node (ref "ENC_SLAVE4") (pin "4") (pinfunction "4_4") (pintype "bidirectional"))
      (node (ref "G15_DRIVER") (pin "1") (pinfunction "1_1") (pintype "passive"))
      (node (ref "GND_1") (pin "1") (pinfunction "1_1") (pintype "passive"))
      (node (ref "GND_1") (pin "2") (pinfunction "2_2") (pintype "passive"))
      (node (ref "GND_1") (pin "3") (pinfunction "3_3") (pintype "passive"))
      (node (ref "GND_1") (pin "4") (pinfunction "4_4") (pintype "passive"))
      (node (ref "GND_1") (pin "5") (pinfunction "5_5") (pintype "passive"))
      (node (ref "GND_2") (pin "1") (pinfunction "1_1") (pintype "passive"))
      (node (ref "GND_2") (pin "2") (pinfunction "2_2") (pintype "passive"))
      (node (ref "GND_2") (pin "3") (pinfunction "3_3") (pintype "passive"))
      (node (ref "GND_2") (pin "4") (pinfunction "4_4") (pintype "passive"))
      (node (ref "GND_2") (pin "5") (pinfunction "5_5") (pintype "passive"))
      (node (ref "GND_3") (pin "1") (pinfunction "1_1") (pintype "passive"))
      (node (ref "GND_3") (pin "2") (pinfunction "2_2") (pintype "passive"))
      (node (ref "GND_3") (pin "3") (pinfunction "3_3") (pintype "passive"))
      (node (ref "GND_3") (pin "4") (pinfunction "4_4") (pintype "passive"))
      (node (ref "GND_3") (pin "5") (pinfunction "5_5") (pintype "passive"))
      (node (ref "I2C1P_MASTER") (pin "4") (pinfunction "4_4") (pintype "passive"))
      (node (ref "I2CP_SLAVE") (pin "4") (pinfunction "4_4") (pintype "passive"))
      (node (ref "IMU_BLOCK2") (pin "3") (pinfunction "3_3") (pintype "bidirectional"))
      (node (ref "IMU_BLOCK3") (pin "3") (pinfunction "3_3") (pintype "bidirectional"))
      (node (ref "IMU_BLOCK4") (pin "3") (pinfunction "3_3") (pintype "bidirectional"))
      (node (ref "IMU_MASTER") (pin "3") (pinfunction "3_3") (pintype "bidirectional"))
      (node (ref "K1") (pin "2") (pinfunction "2_2") (pintype "passive"))
      (node (ref "K1") (pin "P") (pinfunction "P_P") (pintype "passive"))
      (node (ref "LIMIT_SWITCH1") (pin "3") (pinfunction "3_3") (pintype "bidirectional"))
      (node (ref "LIMIT_SWITCH2") (pin "3") (pinfunction "3_3") (pintype "bidirectional"))
      (node (ref "LM358") (pin "4") (pinfunction "4_4") (pintype "passive"))
      (node (ref "M1") (pin "7") (pinfunction "7_7") (pintype "passive"))
      (node (ref "M4") (pin "35") (pinfunction "35_35") (pintype "passive"))
      (node (ref "M4") (pin "36") (pinfunction "36_36") (pintype "passive"))
      (node (ref "M7") (pin "6") (pinfunction "6_6") (pintype "passive"))
      (node (ref "M7") (pin "7") (pinfunction "7_7") (pintype "passive"))
      (node (ref "M8") (pin "1") (pinfunction "GND_1") (pintype "power_in"))
      (node (ref "MASTER") (pin "GD3") (pinfunction "GD3_GD3") (pintype "bidirectional"))
      (node (ref "MASTER") (pin "GD4") (pinfunction "GD4_GD4") (pintype "bidirectional"))
      (node (ref "MASTER") (pin "GND") (pinfunction "GND_GND") (pintype "bidirectional"))
      (node (ref "MASTER") (pin "GND1") (pinfunction "GND1_GND1") (pintype "bidirectional"))
      (node (ref "MASTER") (pin "GND2") (pinfunction "GND2_GND2") (pintype "bidirectional"))
      (node (ref "MASTER") (pin "GND5") (pinfunction "GND5_GND5") (pintype "bidirectional"))
      (node (ref "ODRIVE1") (pin "1") (pinfunction "1_1") (pintype "passive"))
      (node (ref "ODRIVE2") (pin "1") (pinfunction "1_1") (pintype "passive"))
      (node (ref "ODRIVE3") (pin "1") (pinfunction "1_1") (pintype "passive"))
      (node (ref "ODRIVE4") (pin "1") (pinfunction "1_1") (pintype "passive"))
      (node (ref "P1") (pin "1") (pinfunction "1_1") (pintype "bidirectional"))
      (node (ref "P2") (pin "1") (pinfunction "1_1") (pintype "bidirectional"))
      (node (ref "P3") (pin "1") (pinfunction "1_1") (pintype "bidirectional"))
      (node (ref "P4") (pin "1") (pinfunction "1_1") (pintype "bidirectional"))
      (node (ref "PROX_RES") (pin "1") (pinfunction "1_1") (pintype "passive"))
      (node (ref "R13") (pin "2") (pinfunction "2_2") (pintype "passive"))
      (node (ref "R14") (pin "2") (pinfunction "2_2") (pintype "passive"))
      (node (ref "R15") (pin "2") (pinfunction "2_2") (pintype "passive"))
      (node (ref "RST_SWITCH") (pin "3") (pinfunction "3_3") (pintype "passive"))
      (node (ref "RST_SWITCH") (pin "4") (pinfunction "4_4") (pintype "passive"))
      (node (ref "S-4") (pin "35") (pinfunction "35_35") (pintype "passive"))
      (node (ref "S-4") (pin "36") (pinfunction "36_36") (pintype "passive"))
      (node (ref "S-ICSP") (pin "5") (pinfunction "5_5") (pintype "passive"))
      (node (ref "S1") (pin "7") (pinfunction "7_7") (pintype "passive"))
      (node (ref "S7") (pin "6") (pinfunction "6_6") (pintype "passive"))
      (node (ref "S7") (pin "7") (pinfunction "7_7") (pintype "passive"))
      (node (ref "SABER1") (pin "1") (pinfunction "1_1") (pintype "passive"))
      (node (ref "SABER2") (pin "1") (pinfunction "1_1") (pintype "passive"))
      (node (ref "SABER3") (pin "1") (pinfunction "1_1") (pintype "passive"))
      (node (ref "SABER4") (pin "1") (pinfunction "1_1") (pintype "passive"))
      (node (ref "SERVO1") (pin "3") (pinfunction "3_3") (pintype "bidirectional"))
      (node (ref "SERVO2") (pin "3") (pinfunction "3_3") (pintype "bidirectional"))
      (node (ref "SLAVE") (pin "GD3") (pinfunction "GD3_GD3") (pintype "bidirectional"))
      (node (ref "SLAVE") (pin "GD4") (pinfunction "GD4_GD4") (pintype "bidirectional"))
      (node (ref "SLAVE") (pin "GND") (pinfunction "GND_GND") (pintype "bidirectional"))
      (node (ref "SLAVE") (pin "GND1") (pinfunction "GND1_GND1") (pintype "bidirectional"))
      (node (ref "SLAVE") (pin "GND2") (pinfunction "GND2_GND2") (pintype "bidirectional"))
      (node (ref "SLAVE") (pin "GND5") (pinfunction "GND5_GND5") (pintype "bidirectional"))
      (node (ref "STEPPER") (pin "1") (pinfunction "1_1") (pintype "bidirectional"))
      (node (ref "STEPPER") (pin "3") (pinfunction "3_3") (pintype "bidirectional"))
      (node (ref "SUPPLY") (pin "2") (pinfunction "2_2") (pintype "bidirectional"))
      (node (ref "U$2") (pin "2") (pinfunction "2_2") (pintype "bidirectional"))
      (node (ref "U$2") (pin "4") (pinfunction "4_4") (pintype "bidirectional"))
      (node (ref "U$23") (pin "2") (pinfunction "GND_2") (pintype "bidirectional"))
      (node (ref "U$24") (pin "2") (pinfunction "GND_2") (pintype "bidirectional"))
      (node (ref "U$25") (pin "2") (pinfunction "GND_2") (pintype "bidirectional"))
      (node (ref "U$26") (pin "2") (pinfunction "GND_2") (pintype "bidirectional"))
      (node (ref "U$35") (pin "2") (pinfunction "2_2") (pintype "bidirectional"))
      (node (ref "ULN_2003") (pin "8") (pinfunction "8_8") (pintype "passive"))
      (node (ref "VCC-GND") (pin "2") (pinfunction "2_2") (pintype "bidirectional"))
    )
    (net (code "160") (name "MISO") (class "Default")
      (node (ref "MASTER") (pin "MISO") (pinfunction "MISO_MISO") (pintype "bidirectional"))
      (node (ref "U$4") (pin "MISO") (pinfunction "MI_MISO") (pintype "bidirectional"))
    )
    (net (code "161") (name "MOSI") (class "Default")
      (node (ref "MASTER") (pin "MOSI") (pinfunction "MOSI_MOSI") (pintype "bidirectional"))
      (node (ref "U$4") (pin "MOSI") (pinfunction "MO_MOSI") (pintype "bidirectional"))
    )
    (net (code "162") (name "Net-(BUZZER-1)") (class "Default")
      (node (ref "BUZ1") (pin "1") (pinfunction "1_1") (pintype "passive"))
      (node (ref "BUZ2") (pin "1") (pinfunction "1_1") (pintype "passive"))
      (node (ref "BUZZER") (pin "+") (pinfunction "1_+") (pintype "passive"))
    )
    (net (code "163") (name "Net-(C1-+)") (class "Default")
      (node (ref "C1") (pin "1") (pinfunction "+_1") (pintype "passive"))
      (node (ref "LM358") (pin "5") (pinfunction "5_5") (pintype "passive"))
      (node (ref "R1") (pin "1") (pinfunction "1_1") (pintype "passive"))
    )
    (net (code "164") (name "Net-(C2-+)") (class "Default")
      (node (ref "C2") (pin "1") (pinfunction "+_1") (pintype "passive"))
      (node (ref "LM358") (pin "3") (pinfunction "3_3") (pintype "passive"))
      (node (ref "R3") (pin "2") (pinfunction "2_2") (pintype "passive"))
    )
    (net (code "165") (name "Net-(D6-PadA)") (class "Default")
      (node (ref "D6") (pin "A") (pinfunction "A_A") (pintype "passive"))
      (node (ref "ULN_PULL") (pin "2") (pinfunction "2_2") (pintype "passive"))
    )
    (net (code "166") (name "Net-(D7-PadA)") (class "Default")
      (node (ref "D7") (pin "A") (pinfunction "A_A") (pintype "passive"))
      (node (ref "ULN_PULL") (pin "3") (pinfunction "3_3") (pintype "passive"))
    )
    (net (code "167") (name "Net-(D8-PadA)") (class "Default")
      (node (ref "D8") (pin "A") (pinfunction "A_A") (pintype "passive"))
      (node (ref "ULN_PULL") (pin "4") (pinfunction "4_4") (pintype "passive"))
    )
    (net (code "168") (name "Net-(D9-PadA)") (class "Default")
      (node (ref "D9") (pin "A") (pinfunction "A_A") (pintype "passive"))
      (node (ref "ULN_PULL") (pin "5") (pinfunction "5_5") (pintype "passive"))
    )
    (net (code "169") (name "Net-(D10-PadA)") (class "Default")
      (node (ref "D10") (pin "A") (pinfunction "A_A") (pintype "passive"))
      (node (ref "ULN_PULL") (pin "6") (pinfunction "6_6") (pintype "passive"))
    )
    (net (code "170") (name "Net-(DEBUG-S-Pad1)") (class "Default")
      (node (ref "DEBUG-S") (pin "1") (pinfunction "1_1") (pintype "bidirectional"))
      (node (ref "R10") (pin "1") (pinfunction "1_1") (pintype "passive"))
    )
    (net (code "171") (name "Net-(DEBUG-S-Pad2)") (class "Default")
      (node (ref "DEBUG-S") (pin "2") (pinfunction "2_2") (pintype "bidirectional"))
      (node (ref "R9") (pin "1") (pinfunction "1_1") (pintype "passive"))
    )
    (net (code "172") (name "Net-(DEBUG-S-Pad3)") (class "Default")
      (node (ref "DEBUG-S") (pin "3") (pinfunction "3_3") (pintype "bidirectional"))
      (node (ref "R8") (pin "1") (pinfunction "1_1") (pintype "passive"))
    )
    (net (code "173") (name "Net-(DEBUG_M-Pad1)") (class "Default")
      (node (ref "DEBUG_M") (pin "1") (pinfunction "1_1") (pintype "bidirectional"))
      (node (ref "R2") (pin "1") (pinfunction "1_1") (pintype "passive"))
    )
    (net (code "174") (name "Net-(DEBUG_M-Pad2)") (class "Default")
      (node (ref "DEBUG_M") (pin "2") (pinfunction "2_2") (pintype "bidirectional"))
      (node (ref "R4") (pin "1") (pinfunction "1_1") (pintype "passive"))
    )
    (net (code "175") (name "Net-(DEBUG_M-Pad3)") (class "Default")
      (node (ref "DEBUG_M") (pin "3") (pinfunction "3_3") (pintype "bidirectional"))
      (node (ref "R5") (pin "1") (pinfunction "1_1") (pintype "passive"))
    )
    (net (code "176") (name "Net-(DEBUG_M-Pad4)") (class "Default")
      (node (ref "DEBUG_M") (pin "4") (pinfunction "4_4") (pintype "bidirectional"))
      (node (ref "R6") (pin "1") (pinfunction "1_1") (pintype "passive"))
    )
    (net (code "177") (name "Net-(DEBUG_M-Pad5)") (class "Default")
      (node (ref "DEBUG_M") (pin "5") (pinfunction "5_5") (pintype "bidirectional"))
      (node (ref "R7") (pin "1") (pinfunction "1_1") (pintype "passive"))
    )
    (net (code "178") (name "Net-(LED1-PadA)") (class "Default")
      (node (ref "LED1") (pin "A") (pinfunction "A_A") (pintype "passive"))
      (node (ref "PPR5") (pin "1") (pinfunction "1_1") (pintype "passive"))
    )
    (net (code "179") (name "Net-(LED1-PadK)") (class "Default")
      (node (ref "LED1") (pin "K") (pinfunction "K_K") (pintype "passive"))
      (node (ref "R13") (pin "1") (pinfunction "1_1") (pintype "passive"))
    )
    (net (code "180") (name "Net-(LED2-PadA)") (class "Default")
      (node (ref "LED2") (pin "A") (pinfunction "A_A") (pintype "passive"))
      (node (ref "PPR6") (pin "1") (pinfunction "1_1") (pintype "passive"))
    )
    (net (code "181") (name "Net-(LED2-PadK)") (class "Default")
      (node (ref "LED2") (pin "K") (pinfunction "K_K") (pintype "passive"))
      (node (ref "R14") (pin "1") (pinfunction "1_1") (pintype "passive"))
    )
    (net (code "182") (name "Net-(LED3-PadA)") (class "Default")
      (node (ref "LED3") (pin "A") (pinfunction "A_A") (pintype "passive"))
      (node (ref "PPR7") (pin "1") (pinfunction "1_1") (pintype "passive"))
    )
    (net (code "183") (name "Net-(LED3-PadK)") (class "Default")
      (node (ref "LED3") (pin "K") (pinfunction "K_K") (pintype "passive"))
      (node (ref "R15") (pin "1") (pinfunction "1_1") (pintype "passive"))
    )
    (net (code "184") (name "Net-(LED4-PadA)") (class "Default")
      (node (ref "LED4") (pin "A") (pinfunction "A_A") (pintype "passive"))
      (node (ref "PPR8") (pin "1") (pinfunction "1_1") (pintype "passive"))
    )
    (net (code "185") (name "Net-(LED4-PadK)") (class "Default")
      (node (ref "LED4") (pin "K") (pinfunction "K_K") (pintype "passive"))
      (node (ref "R16") (pin "1") (pinfunction "1_1") (pintype "passive"))
    )
    (net (code "186") (name "Net-(M4-Pad18)") (class "Default")
      (node (ref "M4") (pin "18") (pinfunction "18_18") (pintype "passive"))
      (node (ref "MASTER") (pin "D37") (pinfunction "D37_D37") (pintype "bidirectional"))
    )
    (net (code "187") (name "Net-(M4-Pad22)") (class "Default")
      (node (ref "M4") (pin "22") (pinfunction "22_22") (pintype "passive"))
      (node (ref "MASTER") (pin "D41") (pinfunction "D41_D41") (pintype "bidirectional"))
    )
    (net (code "188") (name "Net-(M4-Pad34)") (class "Default")
      (node (ref "M4") (pin "34") (pinfunction "34_34") (pintype "passive"))
      (node (ref "MASTER") (pin "D53") (pinfunction "D53_D53") (pintype "bidirectional"))
    )
    (net (code "189") (name "Net-(M7-Pad1)") (class "Default")
      (node (ref "M7") (pin "1") (pinfunction "1_1") (pintype "passive"))
      (node (ref "MASTER") (pin "-") (pinfunction "-_-") (pintype "bidirectional"))
    )
    (net (code "190") (name "Net-(RESET-Pad3)") (class "Default")
      (node (ref "RESET") (pin "3") (pinfunction "3_3") (pintype "passive"))
      (node (ref "RST_SWITCH") (pin "1") (pinfunction "1_1") (pintype "passive"))
    )
    (net (code "191") (name "Net-(RESET-Pad4)") (class "Default")
      (node (ref "RESET") (pin "4") (pinfunction "4_4") (pintype "passive"))
      (node (ref "RST_SWITCH") (pin "2") (pinfunction "2_2") (pintype "passive"))
    )
    (net (code "192") (name "Net-(S7-Pad1)") (class "Default")
      (node (ref "S7") (pin "1") (pinfunction "1_1") (pintype "passive"))
      (node (ref "SLAVE") (pin "-") (pinfunction "-_-") (pintype "bidirectional"))
    )
    (net (code "193") (name "Net-(S7-Pad2)") (class "Default")
      (node (ref "S7") (pin "2") (pinfunction "2_2") (pintype "passive"))
      (node (ref "SLAVE") (pin "IOREF") (pinfunction "IOREF_IOREF") (pintype "bidirectional"))
    )
    (net (code "194") (name "RST") (class "Default")
      (node (ref "M7") (pin "3") (pinfunction "3_3") (pintype "passive"))
      (node (ref "MASTER") (pin "RST") (pinfunction "RST_RST") (pintype "bidirectional"))
      (node (ref "MASTER") (pin "RST1") (pinfunction "RST1_RST1") (pintype "bidirectional"))
      (node (ref "RESET") (pin "1") (pinfunction "1_1") (pintype "passive"))
      (node (ref "U$4") (pin "RST") (pinfunction "RST_RST") (pintype "bidirectional"))
      (node (ref "U$4") (pin "RST1") (pinfunction "RST1_RST1") (pintype "bidirectional"))
    )
    (net (code "195") (name "S-5V") (class "Default")
      (node (ref "5V") (pin "2") (pinfunction "2_2") (pintype "passive"))
      (node (ref "5V_2") (pin "1") (pinfunction "1_1") (pintype "passive"))
      (node (ref "5V_2") (pin "2") (pinfunction "2_2") (pintype "passive"))
      (node (ref "5V_2") (pin "3") (pinfunction "3_3") (pintype "passive"))
      (node (ref "5V_2") (pin "4") (pinfunction "4_4") (pintype "passive"))
      (node (ref "5V_2") (pin "5") (pinfunction "5_5") (pintype "passive"))
      (node (ref "5V_3") (pin "1") (pinfunction "1_1") (pintype "passive"))
      (node (ref "5V_3") (pin "2") (pinfunction "2_2") (pintype "passive"))
      (node (ref "5V_3") (pin "3") (pinfunction "3_3") (pintype "passive"))
      (node (ref "5V_3") (pin "4") (pinfunction "4_4") (pintype "passive"))
      (node (ref "5V_3") (pin "5") (pinfunction "5_5") (pintype "passive"))
      (node (ref "I2CP_SLAVE") (pin "1") (pinfunction "1_1") (pintype "passive"))
      (node (ref "IMU_BLOCK3") (pin "4") (pinfunction "4_4") (pintype "bidirectional"))
      (node (ref "IMU_BLOCK4") (pin "4") (pinfunction "4_4") (pintype "bidirectional"))
      (node (ref "S-4") (pin "1") (pinfunction "1_1") (pintype "passive"))
      (node (ref "S-4") (pin "2") (pinfunction "2_2") (pintype "passive"))
      (node (ref "S-ICSP") (pin "1") (pinfunction "1_1") (pintype "passive"))
      (node (ref "S7") (pin "5") (pinfunction "5_5") (pintype "passive"))
      (node (ref "SLAVE") (pin "5V") (pinfunction "5V_5V") (pintype "bidirectional"))
      (node (ref "SLAVE") (pin "5V1") (pinfunction "5V1_5V1") (pintype "bidirectional"))
      (node (ref "SLAVE") (pin "5V2") (pinfunction "5V2_5V2") (pintype "bidirectional"))
      (node (ref "SLAVE") (pin "5V3") (pinfunction "5V3_5V3") (pintype "bidirectional"))
    )
    (net (code "196") (name "S-MISO") (class "Default")
      (node (ref "S-ICSP") (pin "2") (pinfunction "2_2") (pintype "passive"))
      (node (ref "SLAVE") (pin "MISO") (pinfunction "MISO_MISO") (pintype "bidirectional"))
    )
    (net (code "197") (name "S-MOSI") (class "Default")
      (node (ref "S-ICSP") (pin "3") (pinfunction "3_3") (pintype "passive"))
      (node (ref "SLAVE") (pin "MOSI") (pinfunction "MOSI_MOSI") (pintype "bidirectional"))
    )
    (net (code "198") (name "S-RST") (class "Default")
      (node (ref "RESET") (pin "2") (pinfunction "2_2") (pintype "passive"))
      (node (ref "S-ICSP") (pin "6") (pinfunction "6_6") (pintype "passive"))
      (node (ref "S7") (pin "3") (pinfunction "3_3") (pintype "passive"))
      (node (ref "SLAVE") (pin "RST") (pinfunction "RST_RST") (pintype "bidirectional"))
      (node (ref "SLAVE") (pin "RST1") (pinfunction "RST1_RST1") (pintype "bidirectional"))
    )
    (net (code "199") (name "S-SCK") (class "Default")
      (node (ref "S-ICSP") (pin "4") (pinfunction "4_4") (pintype "passive"))
      (node (ref "SLAVE") (pin "SCK") (pinfunction "SCK_SCK") (pintype "bidirectional"))
    )
    (net (code "200") (name "S-SCL") (class "Default")
      (node (ref "I2CP_SLAVE") (pin "2") (pinfunction "2_2") (pintype "passive"))
      (node (ref "IMU_BLOCK3") (pin "2") (pinfunction "2_2") (pintype "bidirectional"))
      (node (ref "IMU_BLOCK4") (pin "2") (pinfunction "2_2") (pintype "bidirectional"))
      (node (ref "S-3") (pin "1") (pinfunction "1_1") (pintype "passive"))
      (node (ref "S1") (pin "10") (pinfunction "10_10") (pintype "passive"))
      (node (ref "SLAVE") (pin "SCL") (pinfunction "SCL_SCL") (pintype "bidirectional"))
      (node (ref "SLAVE") (pin "SCLU") (pinfunction "SCLU_SCLU") (pintype "bidirectional"))
    )
    (net (code "201") (name "S-SDA") (class "Default")
      (node (ref "I2CP_SLAVE") (pin "3") (pinfunction "3_3") (pintype "passive"))
      (node (ref "IMU_BLOCK3") (pin "1") (pinfunction "1_1") (pintype "bidirectional"))
      (node (ref "IMU_BLOCK4") (pin "1") (pinfunction "1_1") (pintype "bidirectional"))
      (node (ref "S-3") (pin "2") (pinfunction "2_2") (pintype "passive"))
      (node (ref "S1") (pin "9") (pinfunction "9_9") (pintype "passive"))
      (node (ref "SLAVE") (pin "SDA") (pinfunction "SDA_SDA") (pintype "bidirectional"))
      (node (ref "SLAVE") (pin "SDAU") (pinfunction "SDAU_SDAU") (pintype "bidirectional"))
    )
    (net (code "202") (name "SCK") (class "Default")
      (node (ref "MASTER") (pin "SCK") (pinfunction "SCK_SCK") (pintype "bidirectional"))
      (node (ref "U$4") (pin "SCK") (pinfunction "SC_SCK") (pintype "bidirectional"))
    )
    (net (code "203") (name "SCL") (class "Default")
      (node (ref "I2C1P_MASTER") (pin "2") (pinfunction "2_2") (pintype "passive"))
      (node (ref "IMU_BLOCK2") (pin "2") (pinfunction "2_2") (pintype "bidirectional"))
      (node (ref "IMU_MASTER") (pin "2") (pinfunction "2_2") (pintype "bidirectional"))
      (node (ref "M1") (pin "10") (pinfunction "10_10") (pintype "passive"))
      (node (ref "M3") (pin "1") (pinfunction "1_1") (pintype "passive"))
      (node (ref "MASTER") (pin "SCL") (pinfunction "SCL_SCL") (pintype "bidirectional"))
      (node (ref "MASTER") (pin "SCLU") (pinfunction "SCLU_SCLU") (pintype "bidirectional"))
      (node (ref "U$4") (pin "SCL") (pinfunction "SCL_SCL") (pintype "bidirectional"))
    )
    (net (code "204") (name "SDA") (class "Default")
      (node (ref "I2C1P_MASTER") (pin "3") (pinfunction "3_3") (pintype "passive"))
      (node (ref "IMU_BLOCK2") (pin "1") (pinfunction "1_1") (pintype "bidirectional"))
      (node (ref "IMU_MASTER") (pin "1") (pinfunction "1_1") (pintype "bidirectional"))
      (node (ref "M1") (pin "9") (pinfunction "9_9") (pintype "passive"))
      (node (ref "M3") (pin "2") (pinfunction "2_2") (pintype "passive"))
      (node (ref "MASTER") (pin "SDA") (pinfunction "SDA_SDA") (pintype "bidirectional"))
      (node (ref "MASTER") (pin "SDAU") (pinfunction "SDAU_SDAU") (pintype "bidirectional"))
      (node (ref "U$4") (pin "SDA") (pinfunction "SDA_SDA") (pintype "bidirectional"))
    )
    (net (code "205") (name "VCC") (class "Default")
      (node (ref "AMS1117_1") (pin "1") (pinfunction "IN_1") (pintype "bidirectional"))
      (node (ref "AMS1117_2") (pin "1") (pinfunction "IN_1") (pintype "bidirectional"))
      (node (ref "G15_DRIVER") (pin "2") (pinfunction "2_2") (pintype "passive"))
      (node (ref "K1") (pin "1") (pinfunction "1_1") (pintype "passive"))
      (node (ref "LM358") (pin "8") (pinfunction "8_8") (pintype "passive"))
      (node (ref "P1") (pin "3") (pinfunction "3_3") (pintype "bidirectional"))
      (node (ref "P2") (pin "3") (pinfunction "3_3") (pintype "bidirectional"))
      (node (ref "P3") (pin "3") (pinfunction "3_3") (pintype "bidirectional"))
      (node (ref "P4") (pin "3") (pinfunction "3_3") (pintype "bidirectional"))
      (node (ref "SUPPLY") (pin "1") (pinfunction "1_1") (pintype "bidirectional"))
      (node (ref "U$2") (pin "1") (pinfunction "1_1") (pintype "bidirectional"))
      (node (ref "ULN_2003") (pin "9") (pinfunction "9_9") (pintype "passive"))
      (node (ref "ULN_SUPPLY") (pin "1") (pinfunction "1_1") (pintype "bidirectional"))
      (node (ref "ULN_SUPPLY") (pin "2") (pinfunction "2_2") (pintype "bidirectional"))
      (node (ref "ULN_SUPPLY1") (pin "1") (pinfunction "1_1") (pintype "bidirectional"))
      (node (ref "ULN_SUPPLY1") (pin "2") (pinfunction "2_2") (pintype "bidirectional"))
      (node (ref "VCC-GND") (pin "1") (pinfunction "1_1") (pintype "bidirectional"))
    )
    (net (code "206") (name "unconnected-(K1-PadO)") (class "Default")
      (node (ref "K1") (pin "O") (pinfunction "O_O") (pintype "passive"))
    )
    (net (code "207") (name "unconnected-(M8-IRQ-Pad8)") (class "Default")
      (node (ref "M8") (pin "8") (pinfunction "IRQ_8") (pintype "bidirectional"))
    )
    (net (code "208") (name "unconnected-(R16-Pad2)") (class "Default")
      (node (ref "R16") (pin "2") (pinfunction "2_2") (pintype "passive"))
    )
    (net (code "209") (name "unconnected-(U$3-Pad1)") (class "Default")
      (node (ref "U$3") (pin "1") (pinfunction "1_1") (pintype "bidirectional"))
    )
    (net (code "210") (name "unconnected-(U$4-GD-PadGND1)") (class "Default")
      (node (ref "U$4") (pin "GND1") (pinfunction "GD_GND1") (pintype "bidirectional"))
    )
    (net (code "211") (name "unconnected-(U$4-Pad-)") (class "Default")
      (node (ref "U$4") (pin "-") (pinfunction "-_-") (pintype "bidirectional"))
    )
    (net (code "212") (name "unconnected-(U$4-PadGND)") (class "Default")
      (node (ref "U$4") (pin "GND") (pinfunction "GND_GND") (pintype "bidirectional"))
    )
    (net (code "213") (name "unconnected-(U$4-PadGND2)") (class "Default")
      (node (ref "U$4") (pin "GND2") (pinfunction "GND2_GND2") (pintype "bidirectional"))
    )
    (net (code "214") (name "unconnected-(U$4-PadGND3)") (class "Default")
      (node (ref "U$4") (pin "GND3") (pinfunction "GND3_GND3") (pintype "bidirectional"))
    )
    (net (code "215") (name "unconnected-(U$5-Pad1)") (class "Default")
      (node (ref "U$5") (pin "1") (pinfunction "1_1") (pintype "bidirectional"))
    )
    (net (code "216") (name "unconnected-(U$6-Pad1)") (class "Default")
      (node (ref "U$6") (pin "1") (pinfunction "1_1") (pintype "bidirectional"))
    )
    (net (code "217") (name "unconnected-(U$7-Pad1)") (class "Default")
      (node (ref "U$7") (pin "1") (pinfunction "1_1") (pintype "bidirectional"))
    )
    (net (code "218") (name "unconnected-(U$8-Pad1)") (class "Default")
      (node (ref "U$8") (pin "1") (pinfunction "1_1") (pintype "bidirectional"))
    )
    (net (code "219") (name "unconnected-(U$9-Pad1)") (class "Default")
      (node (ref "U$9") (pin "1") (pinfunction "1_1") (pintype "bidirectional"))
    )
    (net (code "220") (name "unconnected-(ULN_2003-Pad6)") (class "Default")
      (node (ref "ULN_2003") (pin "6") (pinfunction "6_6") (pintype "passive"))
    )
    (net (code "221") (name "unconnected-(ULN_2003-Pad7)") (class "Default")
      (node (ref "ULN_2003") (pin "7") (pinfunction "7_7") (pintype "passive"))
    )
    (net (code "222") (name "unconnected-(ULN_2003-Pad10)") (class "Default")
      (node (ref "ULN_2003") (pin "10") (pinfunction "10_10") (pintype "passive"))
    )
    (net (code "223") (name "unconnected-(ULN_2003-Pad11)") (class "Default")
      (node (ref "ULN_2003") (pin "11") (pinfunction "11_11") (pintype "passive"))
    )
  )
)
